# Sheet1.net
KiCad netlist of a schematic drawn in Altium Designer
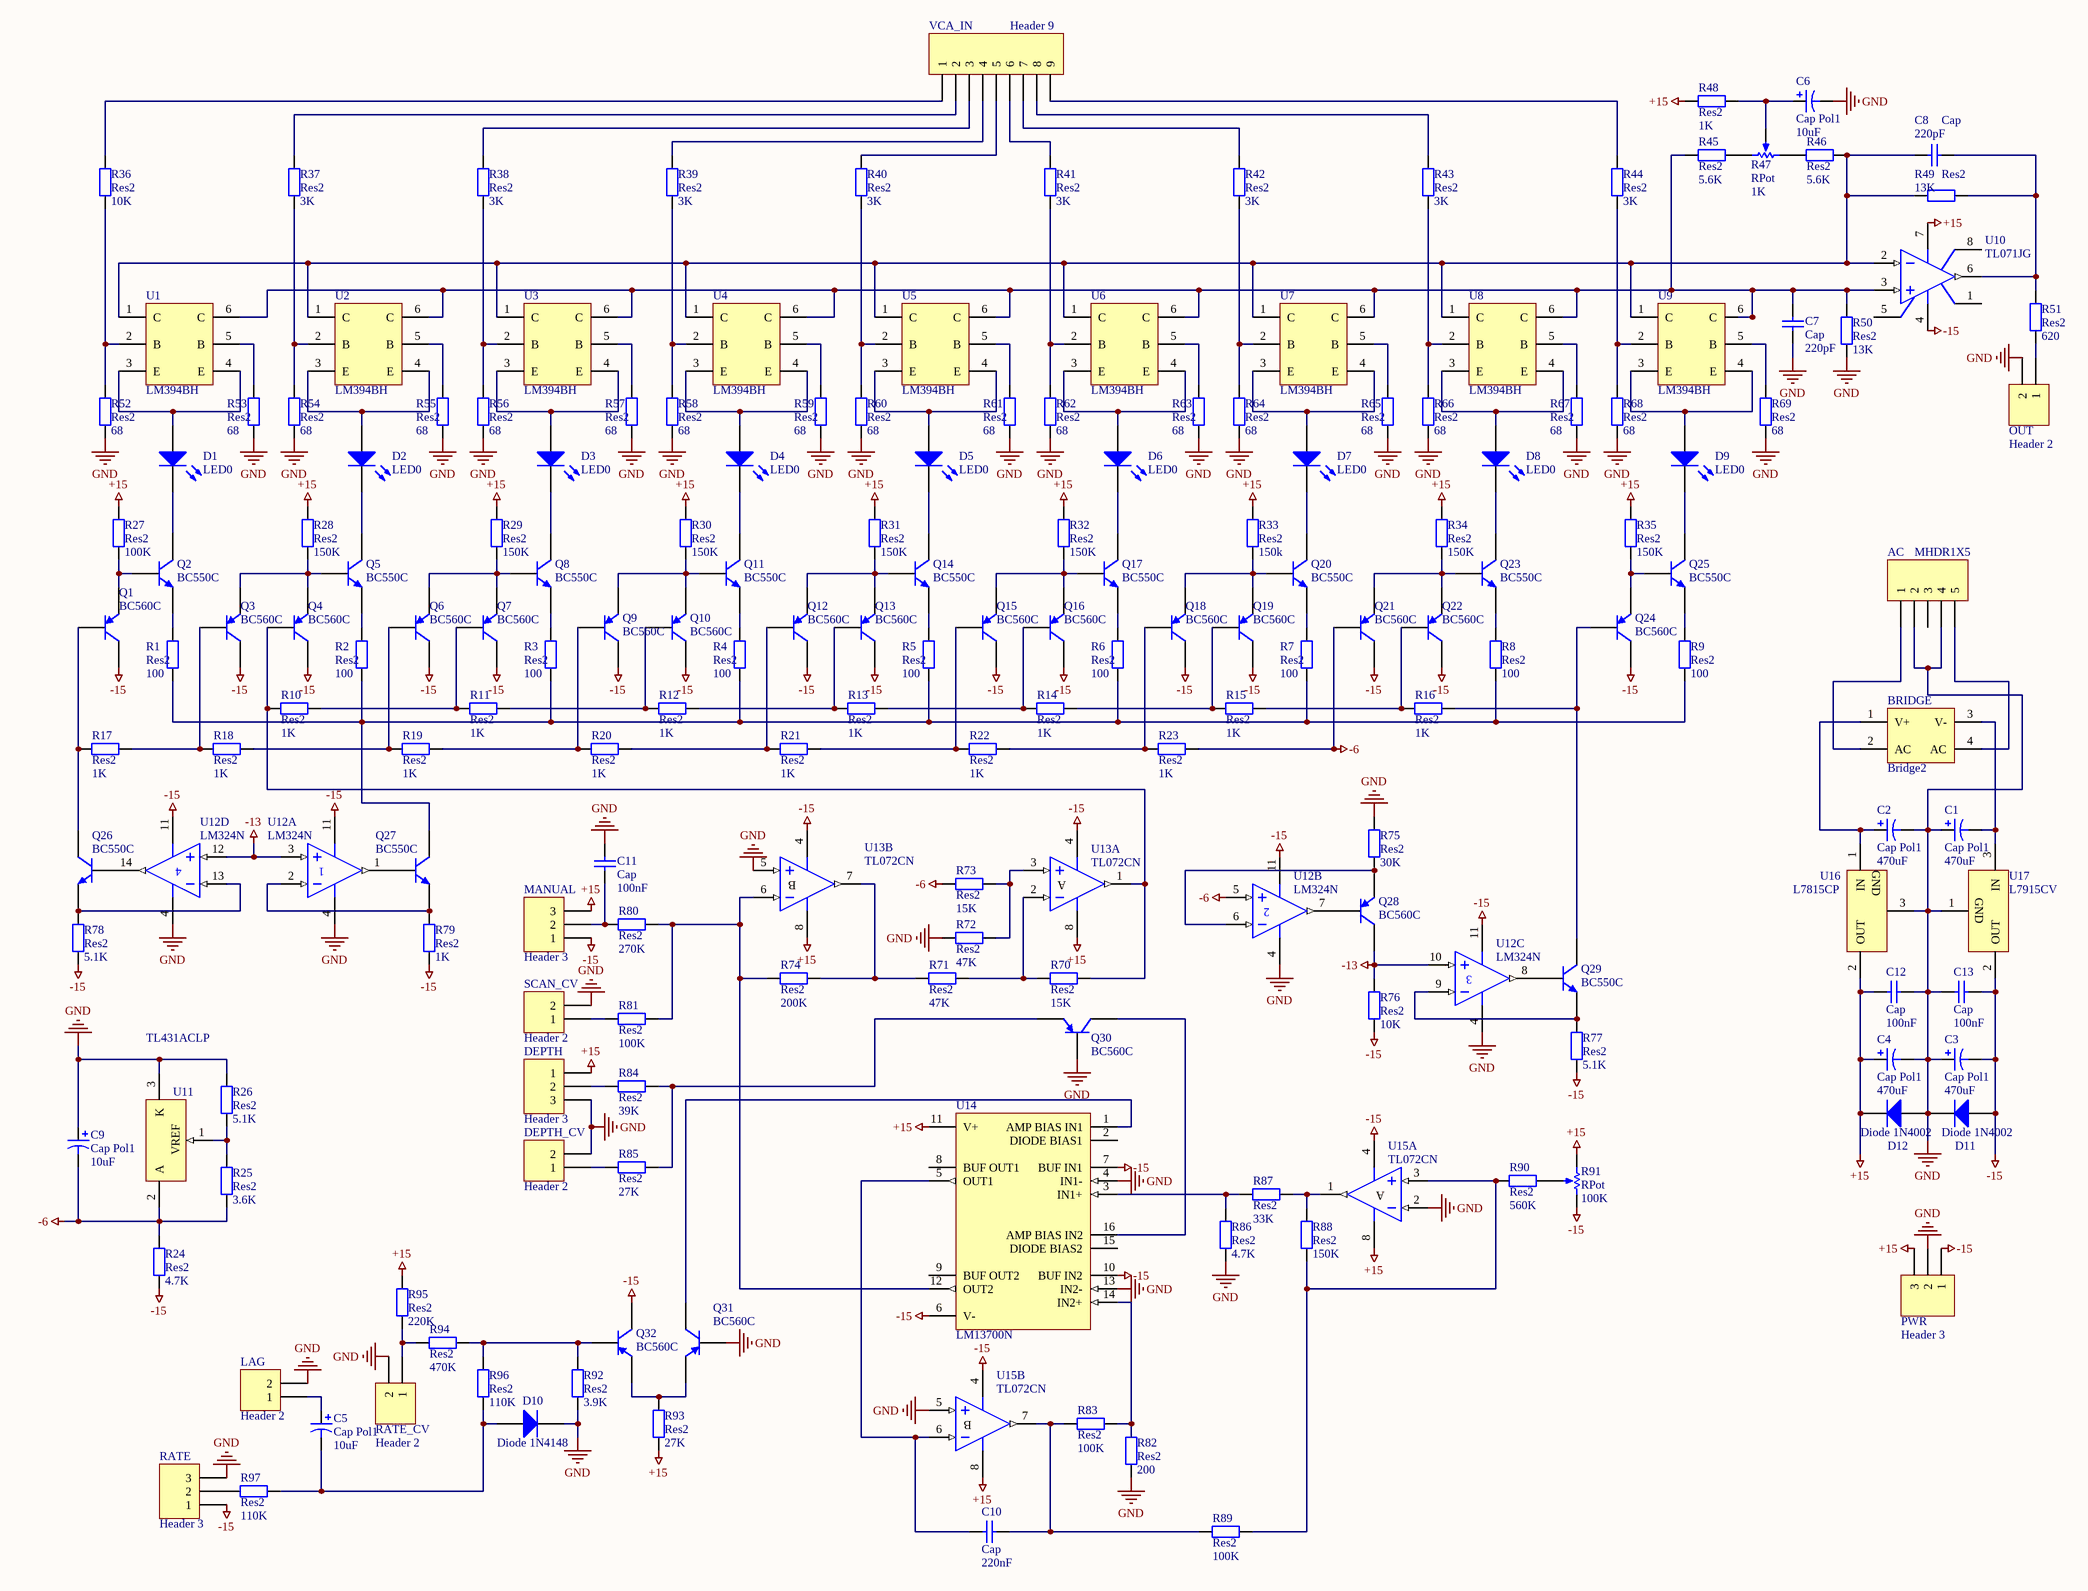
[diagram p0: Sheet1.SchDoc]

(export (version "E")
  (design (tool "Eeschema 10.0.6"))
  (components
    (comp (ref "AC")
      (value "MHDR1X5")
      (footprint "MHDR1X5")
      (description "Header, 5-Pin")
      (fields (field (name "PUBLISHER") "Altium Limited"))
      (libsource (lib "Miscellaneous Connectors") (part "MHDR1X5"))
    )
    (comp (ref "BRIDGE")
      (value "Bridge2")
      (footprint "D-46_6A")
      (description "Diode Bridge")
      (fields (field (name "PUBLISHER") "Altium Limited"))
      (libsource (lib "Miscellaneous Devices") (part "Bridge2"))
    )
    (comp (ref "C1")
      (value "Cap Pol1")
      (footprint "B")
      (description "Polarized Capacitor (Radial)")
      (fields (field (name "ALTIUM_VALUE") "470uF") (field (name "PUBLISHER") "Altium Limited"))
      (libsource (lib "Miscellaneous Devices") (part "Cap Pol1"))
    )
    (comp (ref "C2")
      (value "Cap Pol1")
      (footprint "B")
      (description "Polarized Capacitor (Radial)")
      (fields (field (name "ALTIUM_VALUE") "470uF") (field (name "PUBLISHER") "Altium Limited"))
      (libsource (lib "Miscellaneous Devices") (part "Cap Pol1"))
    )
    (comp (ref "C3")
      (value "Cap Pol1")
      (footprint "B")
      (description "Polarized Capacitor (Radial)")
      (fields (field (name "ALTIUM_VALUE") "470uF") (field (name "PUBLISHER") "Altium Limited"))
      (libsource (lib "Miscellaneous Devices") (part "Cap Pol1"))
    )
    (comp (ref "C4")
      (value "Cap Pol1")
      (footprint "B")
      (description "Polarized Capacitor (Radial)")
      (fields (field (name "ALTIUM_VALUE") "470uF") (field (name "PUBLISHER") "Altium Limited"))
      (libsource (lib "Miscellaneous Devices") (part "Cap Pol1"))
    )
    (comp (ref "C5")
      (value "Cap Pol1")
      (footprint "B")
      (description "Polarized Capacitor (Radial)")
      (fields (field (name "ALTIUM_VALUE") "10uF") (field (name "PUBLISHER") "Altium Limited"))
      (libsource (lib "Miscellaneous Devices") (part "Cap Pol1"))
    )
    (comp (ref "C6")
      (value "Cap Pol1")
      (footprint "B")
      (description "Polarized Capacitor (Radial)")
      (fields (field (name "ALTIUM_VALUE") "10uF") (field (name "PUBLISHER") "Altium Limited"))
      (libsource (lib "Miscellaneous Devices") (part "Cap Pol1"))
    )
    (comp (ref "C7")
      (value "Cap")
      (footprint "VP45-3.2")
      (description "Capacitor")
      (fields (field (name "ALTIUM_VALUE") "220pF") (field (name "PUBLISHER") "Altium Limited"))
      (libsource (lib "Miscellaneous Devices") (part "Cap"))
    )
    (comp (ref "C8")
      (value "Cap")
      (footprint "VP45-3.2")
      (description "Capacitor")
      (fields (field (name "ALTIUM_VALUE") "220pF") (field (name "PUBLISHER") "Altium Limited"))
      (libsource (lib "Miscellaneous Devices") (part "Cap"))
    )
    (comp (ref "C9")
      (value "Cap Pol1")
      (footprint "B")
      (description "Polarized Capacitor (Radial)")
      (fields (field (name "ALTIUM_VALUE") "10uF") (field (name "PUBLISHER") "Altium Limited"))
      (libsource (lib "Miscellaneous Devices") (part "Cap Pol1"))
    )
    (comp (ref "C10")
      (value "Cap")
      (footprint "VP45-3.2")
      (description "Capacitor")
      (fields (field (name "ALTIUM_VALUE") "220nF") (field (name "PUBLISHER") "Altium Limited"))
      (libsource (lib "Miscellaneous Devices") (part "Cap"))
    )
    (comp (ref "C11")
      (value "Cap")
      (footprint "VP45-3.2")
      (description "Capacitor")
      (fields (field (name "ALTIUM_VALUE") "100nF") (field (name "PUBLISHER") "Altium Limited"))
      (libsource (lib "Miscellaneous Devices") (part "Cap"))
    )
    (comp (ref "C12")
      (value "Cap")
      (footprint "VP45-3.2")
      (description "Capacitor")
      (fields (field (name "ALTIUM_VALUE") "100nF") (field (name "PUBLISHER") "Altium Limited"))
      (libsource (lib "Miscellaneous Devices") (part "Cap"))
    )
    (comp (ref "C13")
      (value "Cap")
      (footprint "VP45-3.2")
      (description "Capacitor")
      (fields (field (name "ALTIUM_VALUE") "100nF") (field (name "PUBLISHER") "Altium Limited"))
      (libsource (lib "Miscellaneous Devices") (part "Cap"))
    )
    (comp (ref "D1")
      (value "LED0")
      (footprint "LED-0")
      (description "Typical INFRARED GaAs LED")
      (fields (field (name "PUBLISHER") "Altium Limited"))
      (libsource (lib "Miscellaneous Devices") (part "LED0"))
    )
    (comp (ref "D2")
      (value "LED0")
      (footprint "LED-0")
      (description "Typical INFRARED GaAs LED")
      (fields (field (name "PUBLISHER") "Altium Limited"))
      (libsource (lib "Miscellaneous Devices") (part "LED0"))
    )
    (comp (ref "D3")
      (value "LED0")
      (footprint "LED-0")
      (description "Typical INFRARED GaAs LED")
      (fields (field (name "PUBLISHER") "Altium Limited"))
      (libsource (lib "Miscellaneous Devices") (part "LED0"))
    )
    (comp (ref "D4")
      (value "LED0")
      (footprint "LED-0")
      (description "Typical INFRARED GaAs LED")
      (fields (field (name "PUBLISHER") "Altium Limited"))
      (libsource (lib "Miscellaneous Devices") (part "LED0"))
    )
    (comp (ref "D5")
      (value "LED0")
      (footprint "LED-0")
      (description "Typical INFRARED GaAs LED")
      (fields (field (name "PUBLISHER") "Altium Limited"))
      (libsource (lib "Miscellaneous Devices") (part "LED0"))
    )
    (comp (ref "D6")
      (value "LED0")
      (footprint "LED-0")
      (description "Typical INFRARED GaAs LED")
      (fields (field (name "PUBLISHER") "Altium Limited"))
      (libsource (lib "Miscellaneous Devices") (part "LED0"))
    )
    (comp (ref "D7")
      (value "LED0")
      (footprint "LED-0")
      (description "Typical INFRARED GaAs LED")
      (fields (field (name "PUBLISHER") "Altium Limited"))
      (libsource (lib "Miscellaneous Devices") (part "LED0"))
    )
    (comp (ref "D8")
      (value "LED0")
      (footprint "LED-0")
      (description "Typical INFRARED GaAs LED")
      (fields (field (name "PUBLISHER") "Altium Limited"))
      (libsource (lib "Miscellaneous Devices") (part "LED0"))
    )
    (comp (ref "D9")
      (value "LED0")
      (footprint "LED-0")
      (description "Typical INFRARED GaAs LED")
      (fields (field (name "PUBLISHER") "Altium Limited"))
      (libsource (lib "Miscellaneous Devices") (part "LED0"))
    )
    (comp (ref "D10")
      (value "Diode 1N4148")
      (footprint "DO-35")
      (description "High Conductance Fast Diode")
      (fields (field (name "PUBLISHER") "Altium Limited"))
      (libsource (lib "Miscellaneous Devices") (part "Diode 1N4148"))
    )
    (comp (ref "D11")
      (value "Diode 1N4002")
      (footprint "DO-41")
      (description "1 Amp General Purpose Rectifier")
      (fields (field (name "PUBLISHER") "Altium Limited"))
      (libsource (lib "Miscellaneous Devices") (part "Diode 1N4002"))
    )
    (comp (ref "D12")
      (value "Diode 1N4002")
      (footprint "DO-41")
      (description "1 Amp General Purpose Rectifier")
      (fields (field (name "PUBLISHER") "Altium Limited"))
      (libsource (lib "Miscellaneous Devices") (part "Diode 1N4002"))
    )
    (comp (ref "DEPTH")
      (value "Header 3")
      (footprint "HDR1X3")
      (description "Header, 3-Pin")
      (fields (field (name "PUBLISHER") "Altium Limited"))
      (libsource (lib "") (part "Header 3_1"))
    )
    (comp (ref "DEPTH_CV")
      (value "Header 2")
      (footprint "HDR1X2")
      (description "Header, 2-Pin")
      (fields (field (name "PUBLISHER") "Altium Limited"))
      (libsource (lib "") (part "Header 2_1"))
    )
    (comp (ref "LAG")
      (value "Header 2")
      (footprint "HDR1X2")
      (description "Header, 2-Pin")
      (fields (field (name "PUBLISHER") "Altium Limited"))
      (libsource (lib "") (part "Header 2_1"))
    )
    (comp (ref "MANUAL")
      (value "Header 3")
      (footprint "HDR1X3")
      (description "Header, 3-Pin")
      (fields (field (name "PUBLISHER") "Altium Limited"))
      (libsource (lib "Miscellaneous Connectors") (part "Header 3"))
    )
    (comp (ref "OUT")
      (value "Header 2")
      (footprint "HDR1X2")
      (description "Header, 2-Pin")
      (fields (field (name "PUBLISHER") "Altium Limited"))
      (libsource (lib "Miscellaneous Connectors") (part "Header 2"))
    )
    (comp (ref "PWR")
      (value "Header 3")
      (footprint "HDR1X3")
      (description "Header, 3-Pin")
      (fields (field (name "PUBLISHER") "Altium Limited"))
      (libsource (lib "") (part "Header 3_1"))
    )
    (comp (ref "Q1")
      (value "BC560C")
      (footprint "29-04")
      (description "Low Noise Transistor PNP Silicon")
      (fields (field (name "PUBLISHER") "Altium Limited"))
      (libsource (lib "Motorola Discrete BJT") (part "BC560C"))
    )
    (comp (ref "Q2")
      (value "BC550C")
      (footprint "29-04")
      (description "Amplifier Transistor NPN Silicon")
      (fields (field (name "PUBLISHER") "Altium Limited"))
      (libsource (lib "Motorola Discrete BJT") (part "BC548C"))
    )
    (comp (ref "Q3")
      (value "BC560C")
      (footprint "29-04")
      (description "Low Noise Transistor PNP Silicon")
      (fields (field (name "PUBLISHER") "Altium Limited"))
      (libsource (lib "Motorola Discrete BJT") (part "BC560C"))
    )
    (comp (ref "Q4")
      (value "BC560C")
      (footprint "29-04")
      (description "Low Noise Transistor PNP Silicon")
      (fields (field (name "PUBLISHER") "Altium Limited"))
      (libsource (lib "Motorola Discrete BJT") (part "BC560C"))
    )
    (comp (ref "Q5")
      (value "BC550C")
      (footprint "29-04")
      (description "Amplifier Transistor NPN Silicon")
      (fields (field (name "PUBLISHER") "Altium Limited"))
      (libsource (lib "Motorola Discrete BJT") (part "BC548C"))
    )
    (comp (ref "Q6")
      (value "BC560C")
      (footprint "29-04")
      (description "Low Noise Transistor PNP Silicon")
      (fields (field (name "PUBLISHER") "Altium Limited"))
      (libsource (lib "Motorola Discrete BJT") (part "BC560C"))
    )
    (comp (ref "Q7")
      (value "BC560C")
      (footprint "29-04")
      (description "Low Noise Transistor PNP Silicon")
      (fields (field (name "PUBLISHER") "Altium Limited"))
      (libsource (lib "Motorola Discrete BJT") (part "BC560C"))
    )
    (comp (ref "Q8")
      (value "BC550C")
      (footprint "29-04")
      (description "Amplifier Transistor NPN Silicon")
      (fields (field (name "PUBLISHER") "Altium Limited"))
      (libsource (lib "Motorola Discrete BJT") (part "BC548C"))
    )
    (comp (ref "Q9")
      (value "BC560C")
      (footprint "29-04")
      (description "Low Noise Transistor PNP Silicon")
      (fields (field (name "PUBLISHER") "Altium Limited"))
      (libsource (lib "Motorola Discrete BJT") (part "BC560C"))
    )
    (comp (ref "Q10")
      (value "BC560C")
      (footprint "29-04")
      (description "Low Noise Transistor PNP Silicon")
      (fields (field (name "PUBLISHER") "Altium Limited"))
      (libsource (lib "Motorola Discrete BJT") (part "BC560C"))
    )
    (comp (ref "Q11")
      (value "BC550C")
      (footprint "29-04")
      (description "Amplifier Transistor NPN Silicon")
      (fields (field (name "PUBLISHER") "Altium Limited"))
      (libsource (lib "Motorola Discrete BJT") (part "BC548C"))
    )
    (comp (ref "Q12")
      (value "BC560C")
      (footprint "29-04")
      (description "Low Noise Transistor PNP Silicon")
      (fields (field (name "PUBLISHER") "Altium Limited"))
      (libsource (lib "Motorola Discrete BJT") (part "BC560C"))
    )
    (comp (ref "Q13")
      (value "BC560C")
      (footprint "29-04")
      (description "Low Noise Transistor PNP Silicon")
      (fields (field (name "PUBLISHER") "Altium Limited"))
      (libsource (lib "Motorola Discrete BJT") (part "BC560C"))
    )
    (comp (ref "Q14")
      (value "BC550C")
      (footprint "29-04")
      (description "Amplifier Transistor NPN Silicon")
      (fields (field (name "PUBLISHER") "Altium Limited"))
      (libsource (lib "Motorola Discrete BJT") (part "BC548C"))
    )
    (comp (ref "Q15")
      (value "BC560C")
      (footprint "29-04")
      (description "Low Noise Transistor PNP Silicon")
      (fields (field (name "PUBLISHER") "Altium Limited"))
      (libsource (lib "Motorola Discrete BJT") (part "BC560C"))
    )
    (comp (ref "Q16")
      (value "BC560C")
      (footprint "29-04")
      (description "Low Noise Transistor PNP Silicon")
      (fields (field (name "PUBLISHER") "Altium Limited"))
      (libsource (lib "Motorola Discrete BJT") (part "BC560C"))
    )
    (comp (ref "Q17")
      (value "BC550C")
      (footprint "29-04")
      (description "Amplifier Transistor NPN Silicon")
      (fields (field (name "PUBLISHER") "Altium Limited"))
      (libsource (lib "Motorola Discrete BJT") (part "BC548C"))
    )
    (comp (ref "Q18")
      (value "BC560C")
      (footprint "29-04")
      (description "Low Noise Transistor PNP Silicon")
      (fields (field (name "PUBLISHER") "Altium Limited"))
      (libsource (lib "Motorola Discrete BJT") (part "BC560C"))
    )
    (comp (ref "Q19")
      (value "BC560C")
      (footprint "29-04")
      (description "Low Noise Transistor PNP Silicon")
      (fields (field (name "PUBLISHER") "Altium Limited"))
      (libsource (lib "Motorola Discrete BJT") (part "BC560C"))
    )
    (comp (ref "Q20")
      (value "BC550C")
      (footprint "29-04")
      (description "Amplifier Transistor NPN Silicon")
      (fields (field (name "PUBLISHER") "Altium Limited"))
      (libsource (lib "Motorola Discrete BJT") (part "BC548C"))
    )
    (comp (ref "Q21")
      (value "BC560C")
      (footprint "29-04")
      (description "Low Noise Transistor PNP Silicon")
      (fields (field (name "PUBLISHER") "Altium Limited"))
      (libsource (lib "Motorola Discrete BJT") (part "BC560C"))
    )
    (comp (ref "Q22")
      (value "BC560C")
      (footprint "29-04")
      (description "Low Noise Transistor PNP Silicon")
      (fields (field (name "PUBLISHER") "Altium Limited"))
      (libsource (lib "Motorola Discrete BJT") (part "BC560C"))
    )
    (comp (ref "Q23")
      (value "BC550C")
      (footprint "29-04")
      (description "Amplifier Transistor NPN Silicon")
      (fields (field (name "PUBLISHER") "Altium Limited"))
      (libsource (lib "Motorola Discrete BJT") (part "BC548C"))
    )
    (comp (ref "Q24")
      (value "BC560C")
      (footprint "29-04")
      (description "Low Noise Transistor PNP Silicon")
      (fields (field (name "PUBLISHER") "Altium Limited"))
      (libsource (lib "Motorola Discrete BJT") (part "BC560C"))
    )
    (comp (ref "Q25")
      (value "BC550C")
      (footprint "29-04")
      (description "Amplifier Transistor NPN Silicon")
      (fields (field (name "PUBLISHER") "Altium Limited"))
      (libsource (lib "Motorola Discrete BJT") (part "BC548C"))
    )
    (comp (ref "Q26")
      (value "BC550C")
      (footprint "29-04")
      (description "Amplifier Transistor NPN Silicon")
      (fields (field (name "PUBLISHER") "Altium Limited"))
      (libsource (lib "Motorola Discrete BJT") (part "BC548C"))
    )
    (comp (ref "Q27")
      (value "BC550C")
      (footprint "29-04")
      (description "Amplifier Transistor NPN Silicon")
      (fields (field (name "PUBLISHER") "Altium Limited"))
      (libsource (lib "Motorola Discrete BJT") (part "BC548C"))
    )
    (comp (ref "Q28")
      (value "BC560C")
      (footprint "29-04")
      (description "Low Noise Transistor PNP Silicon")
      (fields (field (name "PUBLISHER") "Altium Limited"))
      (libsource (lib "Motorola Discrete BJT") (part "BC560C"))
    )
    (comp (ref "Q29")
      (value "BC550C")
      (footprint "29-04")
      (description "Amplifier Transistor NPN Silicon")
      (fields (field (name "PUBLISHER") "Altium Limited"))
      (libsource (lib "Motorola Discrete BJT") (part "BC548C"))
    )
    (comp (ref "Q30")
      (value "BC560C")
      (footprint "29-04")
      (description "Low Noise Transistor PNP Silicon")
      (fields (field (name "PUBLISHER") "Altium Limited"))
      (libsource (lib "Motorola Discrete BJT") (part "BC560C"))
    )
    (comp (ref "Q31")
      (value "BC560C")
      (footprint "29-04")
      (description "Low Noise Transistor PNP Silicon")
      (fields (field (name "PUBLISHER") "Altium Limited"))
      (libsource (lib "Motorola Discrete BJT") (part "BC560C"))
    )
    (comp (ref "Q32")
      (value "BC560C")
      (footprint "29-04")
      (description "Low Noise Transistor PNP Silicon")
      (fields (field (name "PUBLISHER") "Altium Limited"))
      (libsource (lib "Motorola Discrete BJT") (part "BC560C"))
    )
    (comp (ref "R1")
      (value "Res2")
      (footprint "AXIAL-0.4")
      (description "Resistor")
      (fields (field (name "ALTIUM_VALUE") "100") (field (name "PUBLISHER") "Altium Limited"))
      (libsource (lib "") (part "Res2_1"))
    )
    (comp (ref "R2")
      (value "Res2")
      (footprint "AXIAL-0.4")
      (description "Resistor")
      (fields (field (name "ALTIUM_VALUE") "100") (field (name "PUBLISHER") "Altium Limited"))
      (libsource (lib "") (part "Res2_1"))
    )
    (comp (ref "R3")
      (value "Res2")
      (footprint "AXIAL-0.4")
      (description "Resistor")
      (fields (field (name "ALTIUM_VALUE") "100") (field (name "PUBLISHER") "Altium Limited"))
      (libsource (lib "") (part "Res2_1"))
    )
    (comp (ref "R4")
      (value "Res2")
      (footprint "AXIAL-0.4")
      (description "Resistor")
      (fields (field (name "ALTIUM_VALUE") "100") (field (name "PUBLISHER") "Altium Limited"))
      (libsource (lib "") (part "Res2_1"))
    )
    (comp (ref "R5")
      (value "Res2")
      (footprint "AXIAL-0.4")
      (description "Resistor")
      (fields (field (name "ALTIUM_VALUE") "100") (field (name "PUBLISHER") "Altium Limited"))
      (libsource (lib "") (part "Res2_1"))
    )
    (comp (ref "R6")
      (value "Res2")
      (footprint "AXIAL-0.4")
      (description "Resistor")
      (fields (field (name "ALTIUM_VALUE") "100") (field (name "PUBLISHER") "Altium Limited"))
      (libsource (lib "") (part "Res2_1"))
    )
    (comp (ref "R7")
      (value "Res2")
      (footprint "AXIAL-0.4")
      (description "Resistor")
      (fields (field (name "ALTIUM_VALUE") "100") (field (name "PUBLISHER") "Altium Limited"))
      (libsource (lib "") (part "Res2_1"))
    )
    (comp (ref "R8")
      (value "Res2")
      (footprint "AXIAL-0.4")
      (description "Resistor")
      (fields (field (name "ALTIUM_VALUE") "100") (field (name "PUBLISHER") "Altium Limited"))
      (libsource (lib "") (part "Res2_1"))
    )
    (comp (ref "R9")
      (value "Res2")
      (footprint "AXIAL-0.4")
      (description "Resistor")
      (fields (field (name "ALTIUM_VALUE") "100") (field (name "PUBLISHER") "Altium Limited"))
      (libsource (lib "") (part "Res2_1"))
    )
    (comp (ref "R10")
      (value "Res2")
      (footprint "AXIAL-0.4")
      (description "Resistor")
      (fields (field (name "ALTIUM_VALUE") "1K") (field (name "PUBLISHER") "Altium Limited"))
      (libsource (lib "Miscellaneous Devices") (part "Res2"))
    )
    (comp (ref "R11")
      (value "Res2")
      (footprint "AXIAL-0.4")
      (description "Resistor")
      (fields (field (name "ALTIUM_VALUE") "1K") (field (name "PUBLISHER") "Altium Limited"))
      (libsource (lib "Miscellaneous Devices") (part "Res2"))
    )
    (comp (ref "R12")
      (value "Res2")
      (footprint "AXIAL-0.4")
      (description "Resistor")
      (fields (field (name "ALTIUM_VALUE") "1K") (field (name "PUBLISHER") "Altium Limited"))
      (libsource (lib "Miscellaneous Devices") (part "Res2"))
    )
    (comp (ref "R13")
      (value "Res2")
      (footprint "AXIAL-0.4")
      (description "Resistor")
      (fields (field (name "ALTIUM_VALUE") "1K") (field (name "PUBLISHER") "Altium Limited"))
      (libsource (lib "Miscellaneous Devices") (part "Res2"))
    )
    (comp (ref "R14")
      (value "Res2")
      (footprint "AXIAL-0.4")
      (description "Resistor")
      (fields (field (name "ALTIUM_VALUE") "1K") (field (name "PUBLISHER") "Altium Limited"))
      (libsource (lib "Miscellaneous Devices") (part "Res2"))
    )
    (comp (ref "R15")
      (value "Res2")
      (footprint "AXIAL-0.4")
      (description "Resistor")
      (fields (field (name "ALTIUM_VALUE") "1K") (field (name "PUBLISHER") "Altium Limited"))
      (libsource (lib "Miscellaneous Devices") (part "Res2"))
    )
    (comp (ref "R16")
      (value "Res2")
      (footprint "AXIAL-0.4")
      (description "Resistor")
      (fields (field (name "ALTIUM_VALUE") "1K") (field (name "PUBLISHER") "Altium Limited"))
      (libsource (lib "Miscellaneous Devices") (part "Res2"))
    )
    (comp (ref "R17")
      (value "Res2")
      (footprint "AXIAL-0.4")
      (description "Resistor")
      (fields (field (name "ALTIUM_VALUE") "1K") (field (name "PUBLISHER") "Altium Limited"))
      (libsource (lib "Miscellaneous Devices") (part "Res2"))
    )
    (comp (ref "R18")
      (value "Res2")
      (footprint "AXIAL-0.4")
      (description "Resistor")
      (fields (field (name "ALTIUM_VALUE") "1K") (field (name "PUBLISHER") "Altium Limited"))
      (libsource (lib "Miscellaneous Devices") (part "Res2"))
    )
    (comp (ref "R19")
      (value "Res2")
      (footprint "AXIAL-0.4")
      (description "Resistor")
      (fields (field (name "ALTIUM_VALUE") "1K") (field (name "PUBLISHER") "Altium Limited"))
      (libsource (lib "Miscellaneous Devices") (part "Res2"))
    )
    (comp (ref "R20")
      (value "Res2")
      (footprint "AXIAL-0.4")
      (description "Resistor")
      (fields (field (name "ALTIUM_VALUE") "1K") (field (name "PUBLISHER") "Altium Limited"))
      (libsource (lib "Miscellaneous Devices") (part "Res2"))
    )
    (comp (ref "R21")
      (value "Res2")
      (footprint "AXIAL-0.4")
      (description "Resistor")
      (fields (field (name "ALTIUM_VALUE") "1K") (field (name "PUBLISHER") "Altium Limited"))
      (libsource (lib "Miscellaneous Devices") (part "Res2"))
    )
    (comp (ref "R22")
      (value "Res2")
      (footprint "AXIAL-0.4")
      (description "Resistor")
      (fields (field (name "ALTIUM_VALUE") "1K") (field (name "PUBLISHER") "Altium Limited"))
      (libsource (lib "Miscellaneous Devices") (part "Res2"))
    )
    (comp (ref "R23")
      (value "Res2")
      (footprint "AXIAL-0.4")
      (description "Resistor")
      (fields (field (name "ALTIUM_VALUE") "1K") (field (name "PUBLISHER") "Altium Limited"))
      (libsource (lib "Miscellaneous Devices") (part "Res2"))
    )
    (comp (ref "R24")
      (value "Res2")
      (footprint "AXIAL-0.4")
      (description "Resistor")
      (fields (field (name "ALTIUM_VALUE") "4.7K") (field (name "PUBLISHER") "Altium Limited"))
      (libsource (lib "") (part "Res2_1"))
    )
    (comp (ref "R25")
      (value "Res2")
      (footprint "AXIAL-0.4")
      (description "Resistor")
      (fields (field (name "ALTIUM_VALUE") "3.6K") (field (name "PUBLISHER") "Altium Limited"))
      (libsource (lib "") (part "Res2_1"))
    )
    (comp (ref "R26")
      (value "Res2")
      (footprint "AXIAL-0.4")
      (description "Resistor")
      (fields (field (name "ALTIUM_VALUE") "5.1K") (field (name "PUBLISHER") "Altium Limited"))
      (libsource (lib "") (part "Res2_1"))
    )
    (comp (ref "R27")
      (value "Res2")
      (footprint "AXIAL-0.4")
      (description "Resistor")
      (fields (field (name "ALTIUM_VALUE") "100K") (field (name "PUBLISHER") "Altium Limited"))
      (libsource (lib "") (part "Res2_1"))
    )
    (comp (ref "R28")
      (value "Res2")
      (footprint "AXIAL-0.4")
      (description "Resistor")
      (fields (field (name "ALTIUM_VALUE") "150K") (field (name "PUBLISHER") "Altium Limited"))
      (libsource (lib "") (part "Res2_1"))
    )
    (comp (ref "R29")
      (value "Res2")
      (footprint "AXIAL-0.4")
      (description "Resistor")
      (fields (field (name "ALTIUM_VALUE") "150K") (field (name "PUBLISHER") "Altium Limited"))
      (libsource (lib "") (part "Res2_1"))
    )
    (comp (ref "R30")
      (value "Res2")
      (footprint "AXIAL-0.4")
      (description "Resistor")
      (fields (field (name "ALTIUM_VALUE") "150K") (field (name "PUBLISHER") "Altium Limited"))
      (libsource (lib "") (part "Res2_1"))
    )
    (comp (ref "R31")
      (value "Res2")
      (footprint "AXIAL-0.4")
      (description "Resistor")
      (fields (field (name "ALTIUM_VALUE") "150K") (field (name "PUBLISHER") "Altium Limited"))
      (libsource (lib "") (part "Res2_1"))
    )
    (comp (ref "R32")
      (value "Res2")
      (footprint "AXIAL-0.4")
      (description "Resistor")
      (fields (field (name "ALTIUM_VALUE") "150K") (field (name "PUBLISHER") "Altium Limited"))
      (libsource (lib "") (part "Res2_1"))
    )
    (comp (ref "R33")
      (value "Res2")
      (footprint "AXIAL-0.4")
      (description "Resistor")
      (fields (field (name "ALTIUM_VALUE") "150k") (field (name "PUBLISHER") "Altium Limited"))
      (libsource (lib "") (part "Res2_1"))
    )
    (comp (ref "R34")
      (value "Res2")
      (footprint "AXIAL-0.4")
      (description "Resistor")
      (fields (field (name "ALTIUM_VALUE") "150K") (field (name "PUBLISHER") "Altium Limited"))
      (libsource (lib "") (part "Res2_1"))
    )
    (comp (ref "R35")
      (value "Res2")
      (footprint "AXIAL-0.4")
      (description "Resistor")
      (fields (field (name "ALTIUM_VALUE") "150K") (field (name "PUBLISHER") "Altium Limited"))
      (libsource (lib "") (part "Res2_1"))
    )
    (comp (ref "R36")
      (value "Res2")
      (footprint "AXIAL-0.4")
      (description "Resistor")
      (fields (field (name "ALTIUM_VALUE") "10K") (field (name "PUBLISHER") "Altium Limited"))
      (libsource (lib "") (part "Res2_1"))
    )
    (comp (ref "R37")
      (value "Res2")
      (footprint "AXIAL-0.4")
      (description "Resistor")
      (fields (field (name "ALTIUM_VALUE") "3K") (field (name "PUBLISHER") "Altium Limited"))
      (libsource (lib "") (part "Res2_1"))
    )
    (comp (ref "R38")
      (value "Res2")
      (footprint "AXIAL-0.4")
      (description "Resistor")
      (fields (field (name "ALTIUM_VALUE") "3K") (field (name "PUBLISHER") "Altium Limited"))
      (libsource (lib "") (part "Res2_1"))
    )
    (comp (ref "R39")
      (value "Res2")
      (footprint "AXIAL-0.4")
      (description "Resistor")
      (fields (field (name "ALTIUM_VALUE") "3K") (field (name "PUBLISHER") "Altium Limited"))
      (libsource (lib "") (part "Res2_1"))
    )
    (comp (ref "R40")
      (value "Res2")
      (footprint "AXIAL-0.4")
      (description "Resistor")
      (fields (field (name "ALTIUM_VALUE") "3K") (field (name "PUBLISHER") "Altium Limited"))
      (libsource (lib "") (part "Res2_1"))
    )
    (comp (ref "R41")
      (value "Res2")
      (footprint "AXIAL-0.4")
      (description "Resistor")
      (fields (field (name "ALTIUM_VALUE") "3K") (field (name "PUBLISHER") "Altium Limited"))
      (libsource (lib "") (part "Res2_1"))
    )
    (comp (ref "R42")
      (value "Res2")
      (footprint "AXIAL-0.4")
      (description "Resistor")
      (fields (field (name "ALTIUM_VALUE") "3K") (field (name "PUBLISHER") "Altium Limited"))
      (libsource (lib "") (part "Res2_1"))
    )
    (comp (ref "R43")
      (value "Res2")
      (footprint "AXIAL-0.4")
      (description "Resistor")
      (fields (field (name "ALTIUM_VALUE") "3K") (field (name "PUBLISHER") "Altium Limited"))
      (libsource (lib "") (part "Res2_1"))
    )
    (comp (ref "R44")
      (value "Res2")
      (footprint "AXIAL-0.4")
      (description "Resistor")
      (fields (field (name "ALTIUM_VALUE") "3K") (field (name "PUBLISHER") "Altium Limited"))
      (libsource (lib "") (part "Res2_1"))
    )
    (comp (ref "R45")
      (value "Res2")
      (footprint "AXIAL-0.4")
      (description "Resistor")
      (fields (field (name "ALTIUM_VALUE") "5.6K") (field (name "PUBLISHER") "Altium Limited"))
      (libsource (lib "") (part "Res2_3"))
    )
    (comp (ref "R46")
      (value "Res2")
      (footprint "AXIAL-0.4")
      (description "Resistor")
      (fields (field (name "ALTIUM_VALUE") "5.6K") (field (name "PUBLISHER") "Altium Limited"))
      (libsource (lib "") (part "Res2_3"))
    )
    (comp (ref "R47")
      (value "RPot")
      (footprint "VR5")
      (description "Potentiometer")
      (fields (field (name "ALTIUM_VALUE") "1K") (field (name "PUBLISHER") "Altium Limited"))
      (libsource (lib "Miscellaneous Devices") (part "RPot"))
    )
    (comp (ref "R48")
      (value "Res2")
      (footprint "AXIAL-0.4")
      (description "Resistor")
      (fields (field (name "ALTIUM_VALUE") "1K") (field (name "PUBLISHER") "Altium Limited"))
      (libsource (lib "") (part "Res2_3"))
    )
    (comp (ref "R49")
      (value "Res2")
      (footprint "AXIAL-0.4")
      (description "Resistor")
      (fields (field (name "ALTIUM_VALUE") "13K") (field (name "PUBLISHER") "Altium Limited"))
      (libsource (lib "") (part "Res2_3"))
    )
    (comp (ref "R50")
      (value "Res2")
      (footprint "AXIAL-0.4")
      (description "Resistor")
      (fields (field (name "ALTIUM_VALUE") "13K") (field (name "PUBLISHER") "Altium Limited"))
      (libsource (lib "") (part "Res2_1"))
    )
    (comp (ref "R51")
      (value "Res2")
      (footprint "AXIAL-0.4")
      (description "Resistor")
      (fields (field (name "ALTIUM_VALUE") "620") (field (name "PUBLISHER") "Altium Limited"))
      (libsource (lib "") (part "Res2_1"))
    )
    (comp (ref "R52")
      (value "Res2")
      (footprint "AXIAL-0.4")
      (description "Resistor")
      (fields (field (name "ALTIUM_VALUE") "68") (field (name "PUBLISHER") "Altium Limited"))
      (libsource (lib "") (part "Res2_1"))
    )
    (comp (ref "R53")
      (value "Res2")
      (footprint "AXIAL-0.4")
      (description "Resistor")
      (fields (field (name "ALTIUM_VALUE") "68") (field (name "PUBLISHER") "Altium Limited"))
      (libsource (lib "") (part "Res2_1"))
    )
    (comp (ref "R54")
      (value "Res2")
      (footprint "AXIAL-0.4")
      (description "Resistor")
      (fields (field (name "ALTIUM_VALUE") "68") (field (name "PUBLISHER") "Altium Limited"))
      (libsource (lib "") (part "Res2_1"))
    )
    (comp (ref "R55")
      (value "Res2")
      (footprint "AXIAL-0.4")
      (description "Resistor")
      (fields (field (name "ALTIUM_VALUE") "68") (field (name "PUBLISHER") "Altium Limited"))
      (libsource (lib "") (part "Res2_1"))
    )
    (comp (ref "R56")
      (value "Res2")
      (footprint "AXIAL-0.4")
      (description "Resistor")
      (fields (field (name "ALTIUM_VALUE") "68") (field (name "PUBLISHER") "Altium Limited"))
      (libsource (lib "") (part "Res2_1"))
    )
    (comp (ref "R57")
      (value "Res2")
      (footprint "AXIAL-0.4")
      (description "Resistor")
      (fields (field (name "ALTIUM_VALUE") "68") (field (name "PUBLISHER") "Altium Limited"))
      (libsource (lib "") (part "Res2_1"))
    )
    (comp (ref "R58")
      (value "Res2")
      (footprint "AXIAL-0.4")
      (description "Resistor")
      (fields (field (name "ALTIUM_VALUE") "68") (field (name "PUBLISHER") "Altium Limited"))
      (libsource (lib "") (part "Res2_1"))
    )
    (comp (ref "R59")
      (value "Res2")
      (footprint "AXIAL-0.4")
      (description "Resistor")
      (fields (field (name "ALTIUM_VALUE") "68") (field (name "PUBLISHER") "Altium Limited"))
      (libsource (lib "") (part "Res2_1"))
    )
    (comp (ref "R60")
      (value "Res2")
      (footprint "AXIAL-0.4")
      (description "Resistor")
      (fields (field (name "ALTIUM_VALUE") "68") (field (name "PUBLISHER") "Altium Limited"))
      (libsource (lib "") (part "Res2_1"))
    )
    (comp (ref "R61")
      (value "Res2")
      (footprint "AXIAL-0.4")
      (description "Resistor")
      (fields (field (name "ALTIUM_VALUE") "68") (field (name "PUBLISHER") "Altium Limited"))
      (libsource (lib "") (part "Res2_1"))
    )
    (comp (ref "R62")
      (value "Res2")
      (footprint "AXIAL-0.4")
      (description "Resistor")
      (fields (field (name "ALTIUM_VALUE") "68") (field (name "PUBLISHER") "Altium Limited"))
      (libsource (lib "") (part "Res2_1"))
    )
    (comp (ref "R63")
      (value "Res2")
      (footprint "AXIAL-0.4")
      (description "Resistor")
      (fields (field (name "ALTIUM_VALUE") "68") (field (name "PUBLISHER") "Altium Limited"))
      (libsource (lib "") (part "Res2_1"))
    )
    (comp (ref "R64")
      (value "Res2")
      (footprint "AXIAL-0.4")
      (description "Resistor")
      (fields (field (name "ALTIUM_VALUE") "68") (field (name "PUBLISHER") "Altium Limited"))
      (libsource (lib "") (part "Res2_1"))
    )
    (comp (ref "R65")
      (value "Res2")
      (footprint "AXIAL-0.4")
      (description "Resistor")
      (fields (field (name "ALTIUM_VALUE") "68") (field (name "PUBLISHER") "Altium Limited"))
      (libsource (lib "") (part "Res2_1"))
    )
    (comp (ref "R66")
      (value "Res2")
      (footprint "AXIAL-0.4")
      (description "Resistor")
      (fields (field (name "ALTIUM_VALUE") "68") (field (name "PUBLISHER") "Altium Limited"))
      (libsource (lib "") (part "Res2_1"))
    )
    (comp (ref "R67")
      (value "Res2")
      (footprint "AXIAL-0.4")
      (description "Resistor")
      (fields (field (name "ALTIUM_VALUE") "68") (field (name "PUBLISHER") "Altium Limited"))
      (libsource (lib "") (part "Res2_1"))
    )
    (comp (ref "R68")
      (value "Res2")
      (footprint "AXIAL-0.4")
      (description "Resistor")
      (fields (field (name "ALTIUM_VALUE") "68") (field (name "PUBLISHER") "Altium Limited"))
      (libsource (lib "") (part "Res2_1"))
    )
    (comp (ref "R69")
      (value "Res2")
      (footprint "AXIAL-0.4")
      (description "Resistor")
      (fields (field (name "ALTIUM_VALUE") "68") (field (name "PUBLISHER") "Altium Limited"))
      (libsource (lib "") (part "Res2_1"))
    )
    (comp (ref "R70")
      (value "Res2")
      (footprint "AXIAL-0.4")
      (description "Resistor")
      (fields (field (name "ALTIUM_VALUE") "15K") (field (name "PUBLISHER") "Altium Limited"))
      (libsource (lib "Miscellaneous Devices") (part "Res2"))
    )
    (comp (ref "R71")
      (value "Res2")
      (footprint "AXIAL-0.4")
      (description "Resistor")
      (fields (field (name "ALTIUM_VALUE") "47K") (field (name "PUBLISHER") "Altium Limited"))
      (libsource (lib "Miscellaneous Devices") (part "Res2"))
    )
    (comp (ref "R72")
      (value "Res2")
      (footprint "AXIAL-0.4")
      (description "Resistor")
      (fields (field (name "ALTIUM_VALUE") "47K") (field (name "PUBLISHER") "Altium Limited"))
      (libsource (lib "") (part "Res2_3"))
    )
    (comp (ref "R73")
      (value "Res2")
      (footprint "AXIAL-0.4")
      (description "Resistor")
      (fields (field (name "ALTIUM_VALUE") "15K") (field (name "PUBLISHER") "Altium Limited"))
      (libsource (lib "Miscellaneous Devices") (part "Res2"))
    )
    (comp (ref "R74")
      (value "Res2")
      (footprint "AXIAL-0.4")
      (description "Resistor")
      (fields (field (name "ALTIUM_VALUE") "200K") (field (name "PUBLISHER") "Altium Limited"))
      (libsource (lib "Miscellaneous Devices") (part "Res2"))
    )
    (comp (ref "R75")
      (value "Res2")
      (footprint "AXIAL-0.4")
      (description "Resistor")
      (fields (field (name "ALTIUM_VALUE") "30K") (field (name "PUBLISHER") "Altium Limited"))
      (libsource (lib "") (part "Res2_1"))
    )
    (comp (ref "R76")
      (value "Res2")
      (footprint "AXIAL-0.4")
      (description "Resistor")
      (fields (field (name "ALTIUM_VALUE") "10K") (field (name "PUBLISHER") "Altium Limited"))
      (libsource (lib "") (part "Res2_1"))
    )
    (comp (ref "R77")
      (value "Res2")
      (footprint "AXIAL-0.4")
      (description "Resistor")
      (fields (field (name "ALTIUM_VALUE") "5.1K") (field (name "PUBLISHER") "Altium Limited"))
      (libsource (lib "") (part "Res2_1"))
    )
    (comp (ref "R78")
      (value "Res2")
      (footprint "AXIAL-0.4")
      (description "Resistor")
      (fields (field (name "ALTIUM_VALUE") "5.1K") (field (name "PUBLISHER") "Altium Limited"))
      (libsource (lib "") (part "Res2_1"))
    )
    (comp (ref "R79")
      (value "Res2")
      (footprint "AXIAL-0.4")
      (description "Resistor")
      (fields (field (name "ALTIUM_VALUE") "1K") (field (name "PUBLISHER") "Altium Limited"))
      (libsource (lib "") (part "Res2_1"))
    )
    (comp (ref "R80")
      (value "Res2")
      (footprint "AXIAL-0.4")
      (description "Resistor")
      (fields (field (name "ALTIUM_VALUE") "270K") (field (name "PUBLISHER") "Altium Limited"))
      (libsource (lib "Miscellaneous Devices") (part "Res2"))
    )
    (comp (ref "R81")
      (value "Res2")
      (footprint "AXIAL-0.4")
      (description "Resistor")
      (fields (field (name "ALTIUM_VALUE") "100K") (field (name "PUBLISHER") "Altium Limited"))
      (libsource (lib "Miscellaneous Devices") (part "Res2"))
    )
    (comp (ref "R82")
      (value "Res2")
      (footprint "AXIAL-0.4")
      (description "Resistor")
      (fields (field (name "ALTIUM_VALUE") "200") (field (name "PUBLISHER") "Altium Limited"))
      (libsource (lib "Miscellaneous Devices") (part "Res2"))
    )
    (comp (ref "R83")
      (value "Res2")
      (footprint "AXIAL-0.4")
      (description "Resistor")
      (fields (field (name "ALTIUM_VALUE") "100K") (field (name "PUBLISHER") "Altium Limited"))
      (libsource (lib "") (part "Res2_2"))
    )
    (comp (ref "R84")
      (value "Res2")
      (footprint "AXIAL-0.4")
      (description "Resistor")
      (fields (field (name "ALTIUM_VALUE") "39K") (field (name "PUBLISHER") "Altium Limited"))
      (libsource (lib "Miscellaneous Devices") (part "Res2"))
    )
    (comp (ref "R85")
      (value "Res2")
      (footprint "AXIAL-0.4")
      (description "Resistor")
      (fields (field (name "ALTIUM_VALUE") "27K") (field (name "PUBLISHER") "Altium Limited"))
      (libsource (lib "Miscellaneous Devices") (part "Res2"))
    )
    (comp (ref "R86")
      (value "Res2")
      (footprint "AXIAL-0.4")
      (description "Resistor")
      (fields (field (name "ALTIUM_VALUE") "4.7K") (field (name "PUBLISHER") "Altium Limited"))
      (libsource (lib "") (part "Res2_2"))
    )
    (comp (ref "R87")
      (value "Res2")
      (footprint "AXIAL-0.4")
      (description "Resistor")
      (fields (field (name "ALTIUM_VALUE") "33K") (field (name "PUBLISHER") "Altium Limited"))
      (libsource (lib "") (part "Res2_3"))
    )
    (comp (ref "R88")
      (value "Res2")
      (footprint "AXIAL-0.4")
      (description "Resistor")
      (fields (field (name "ALTIUM_VALUE") "150K") (field (name "PUBLISHER") "Altium Limited"))
      (libsource (lib "") (part "Res2_1"))
    )
    (comp (ref "R89")
      (value "Res2")
      (footprint "AXIAL-0.4")
      (description "Resistor")
      (fields (field (name "ALTIUM_VALUE") "100K") (field (name "PUBLISHER") "Altium Limited"))
      (libsource (lib "") (part "Res2_3"))
    )
    (comp (ref "R90")
      (value "Res2")
      (footprint "AXIAL-0.4")
      (description "Resistor")
      (fields (field (name "ALTIUM_VALUE") "560K") (field (name "PUBLISHER") "Altium Limited"))
      (libsource (lib "Miscellaneous Devices") (part "Res2"))
    )
    (comp (ref "R91")
      (value "RPot")
      (footprint "VR5")
      (description "Potentiometer")
      (fields (field (name "ALTIUM_VALUE") "100K") (field (name "PUBLISHER") "Altium Limited"))
      (libsource (lib "Miscellaneous Devices") (part "RPot"))
    )
    (comp (ref "R92")
      (value "Res2")
      (footprint "AXIAL-0.4")
      (description "Resistor")
      (fields (field (name "ALTIUM_VALUE") "3.9K") (field (name "PUBLISHER") "Altium Limited"))
      (libsource (lib "") (part "Res2_1"))
    )
    (comp (ref "R93")
      (value "Res2")
      (footprint "AXIAL-0.4")
      (description "Resistor")
      (fields (field (name "ALTIUM_VALUE") "27K") (field (name "PUBLISHER") "Altium Limited"))
      (libsource (lib "") (part "Res2_1"))
    )
    (comp (ref "R94")
      (value "Res2")
      (footprint "AXIAL-0.4")
      (description "Resistor")
      (fields (field (name "ALTIUM_VALUE") "470K") (field (name "PUBLISHER") "Altium Limited"))
      (libsource (lib "Miscellaneous Devices") (part "Res2"))
    )
    (comp (ref "R95")
      (value "Res2")
      (footprint "AXIAL-0.4")
      (description "Resistor")
      (fields (field (name "ALTIUM_VALUE") "220K") (field (name "PUBLISHER") "Altium Limited"))
      (libsource (lib "") (part "Res2_1"))
    )
    (comp (ref "R96")
      (value "Res2")
      (footprint "AXIAL-0.4")
      (description "Resistor")
      (fields (field (name "ALTIUM_VALUE") "110K") (field (name "PUBLISHER") "Altium Limited"))
      (libsource (lib "") (part "Res2_1"))
    )
    (comp (ref "R97")
      (value "Res2")
      (footprint "AXIAL-0.4")
      (description "Resistor")
      (fields (field (name "ALTIUM_VALUE") "110K") (field (name "PUBLISHER") "Altium Limited"))
      (libsource (lib "Miscellaneous Devices") (part "Res2"))
    )
    (comp (ref "RATE")
      (value "Header 3")
      (footprint "HDR1X3")
      (description "Header, 3-Pin")
      (fields (field (name "PUBLISHER") "Altium Limited"))
      (libsource (lib "Miscellaneous Connectors") (part "Header 3"))
    )
    (comp (ref "RATE_CV")
      (value "Header 2")
      (footprint "HDR1X2")
      (description "Header, 2-Pin")
      (fields (field (name "PUBLISHER") "Altium Limited"))
      (libsource (lib "Miscellaneous Connectors") (part "Header 2"))
    )
    (comp (ref "SCAN_CV")
      (value "Header 2")
      (footprint "HDR1X2")
      (description "Header, 2-Pin")
      (fields (field (name "PUBLISHER") "Altium Limited"))
      (libsource (lib "") (part "Header 2_1"))
    )
    (comp (ref "U1")
      (value "LM394BH")
      (footprint "H06C")
      (description "Supermatch Pair")
      (fields
        (field (name "MANUFACTURER") "National Semiconductor")
        (field (name "DIGIKEYPARTNUMBER") "LM394BH-ND")
        (field (name "PUBLISHER") "Altium Limited")
      )
      (libsource (lib "NSC Amplifier") (part "LM394BH"))
    )
    (comp (ref "U2")
      (value "LM394BH")
      (footprint "H06C")
      (description "Supermatch Pair")
      (fields
        (field (name "MANUFACTURER") "National Semiconductor")
        (field (name "DIGIKEYPARTNUMBER") "LM394BH-ND")
        (field (name "PUBLISHER") "Altium Limited")
      )
      (libsource (lib "NSC Amplifier") (part "LM394BH"))
    )
    (comp (ref "U3")
      (value "LM394BH")
      (footprint "H06C")
      (description "Supermatch Pair")
      (fields
        (field (name "MANUFACTURER") "National Semiconductor")
        (field (name "DIGIKEYPARTNUMBER") "LM394BH-ND")
        (field (name "PUBLISHER") "Altium Limited")
      )
      (libsource (lib "NSC Amplifier") (part "LM394BH"))
    )
    (comp (ref "U4")
      (value "LM394BH")
      (footprint "H06C")
      (description "Supermatch Pair")
      (fields
        (field (name "MANUFACTURER") "National Semiconductor")
        (field (name "DIGIKEYPARTNUMBER") "LM394BH-ND")
        (field (name "PUBLISHER") "Altium Limited")
      )
      (libsource (lib "NSC Amplifier") (part "LM394BH"))
    )
    (comp (ref "U5")
      (value "LM394BH")
      (footprint "H06C")
      (description "Supermatch Pair")
      (fields
        (field (name "MANUFACTURER") "National Semiconductor")
        (field (name "DIGIKEYPARTNUMBER") "LM394BH-ND")
        (field (name "PUBLISHER") "Altium Limited")
      )
      (libsource (lib "NSC Amplifier") (part "LM394BH"))
    )
    (comp (ref "U6")
      (value "LM394BH")
      (footprint "H06C")
      (description "Supermatch Pair")
      (fields
        (field (name "MANUFACTURER") "National Semiconductor")
        (field (name "DIGIKEYPARTNUMBER") "LM394BH-ND")
        (field (name "PUBLISHER") "Altium Limited")
      )
      (libsource (lib "NSC Amplifier") (part "LM394BH"))
    )
    (comp (ref "U7")
      (value "LM394BH")
      (footprint "H06C")
      (description "Supermatch Pair")
      (fields
        (field (name "MANUFACTURER") "National Semiconductor")
        (field (name "DIGIKEYPARTNUMBER") "LM394BH-ND")
        (field (name "PUBLISHER") "Altium Limited")
      )
      (libsource (lib "NSC Amplifier") (part "LM394BH"))
    )
    (comp (ref "U8")
      (value "LM394BH")
      (footprint "H06C")
      (description "Supermatch Pair")
      (fields
        (field (name "MANUFACTURER") "National Semiconductor")
        (field (name "DIGIKEYPARTNUMBER") "LM394BH-ND")
        (field (name "PUBLISHER") "Altium Limited")
      )
      (libsource (lib "NSC Amplifier") (part "LM394BH"))
    )
    (comp (ref "U9")
      (value "LM394BH")
      (footprint "H06C")
      (description "Supermatch Pair")
      (fields
        (field (name "MANUFACTURER") "National Semiconductor")
        (field (name "DIGIKEYPARTNUMBER") "LM394BH-ND")
        (field (name "PUBLISHER") "Altium Limited")
      )
      (libsource (lib "NSC Amplifier") (part "LM394BH"))
    )
    (comp (ref "U10")
      (value "TL071JG")
      (footprint "JG008")
      (description "Low-Noise JFET-Input Operational Amplifier")
      (fields (field (name "PUBLISHER") "Altium Limited"))
      (libsource (lib "TI Operational Amplifier") (part "TL071JG"))
    )
    (comp (ref "U11")
      (value "TL431ACLP")
      (footprint "LP03")
      (description "Adjustable Precision Shunt Regulator")
      (fields (field (name "PUBLISHER") "Altium Limited"))
      (libsource (lib "TI Power Mgt Voltage Regulator") (part "TL431ACLP"))
    )
    (comp (ref "U12")
      (value "LM324N")
      (footprint "646-06")
      (description "Quad Low-Power Operational Amplifier")
      (fields (field (name "PUBLISHER") "Altium Limited"))
      (libsource (lib "Motorola Amplifier Operational Amplifier") (part "LM324N"))
    )
    (comp (ref "U13")
      (value "TL072CN")
      (footprint "DIP8")
      (description "Low-Noise J-FET Dual Operational Amplifier")
      (fields (field (name "PUBLISHER") "Altium Limited"))
      (libsource (lib "ST Operational Amplifier") (part "TL072CN"))
    )
    (comp (ref "U14")
      (value "LM13700N")
      (footprint "N16E")
      (description "Dual Operational Transconductance Amplifier with Linearizing Diodes and Buffers")
      (fields
        (field (name "MANUFACTURER") "National Semiconductor")
        (field (name "DIGIKEYPARTNUMBER") "LM13700N-ND")
        (field (name "PUBLISHER") "Altium Limited")
      )
      (libsource (lib "NSC Amplifier") (part "LM13700N"))
    )
    (comp (ref "U15")
      (value "TL072CN")
      (footprint "DIP8")
      (description "Low-Noise J-FET Dual Operational Amplifier")
      (fields (field (name "PUBLISHER") "Altium Limited"))
      (libsource (lib "ST Operational Amplifier") (part "TL072CN"))
    )
    (comp (ref "U16")
      (value "L7815CP")
      (footprint "ISOWATT220AB")
      (description "Positive Voltage Regulator")
      (fields (field (name "PUBLISHER") "Altium Limited"))
      (libsource (lib "ST Power Mgt Voltage Regulator") (part "L7815CP"))
    )
    (comp (ref "U17")
      (value "L7915CV")
      (footprint "TO220V")
      (description "Negative Voltage Regulator")
      (fields (field (name "PUBLISHER") "Altium Limited"))
      (libsource (lib "ST Power Mgt Voltage Regulator") (part "L7915CV"))
    )
    (comp (ref "VCA_IN")
      (value "Header 9")
      (footprint "HDR1X9")
      (description "Header, 9-Pin")
      (fields (field (name "PUBLISHER") "Altium Limited"))
      (libsource (lib "Miscellaneous Connectors") (part "Header 9"))
    )
  )
  (nets
    (net (code "1") (name "+15") (class "Default")
      (node (ref "C12") (pin "1") (pinfunction "1_1") (pintype "passive"))
      (node (ref "C4") (pin "1") (pinfunction "1_1") (pintype "passive"))
      (node (ref "D12") (pin "2") (pinfunction "K_2") (pintype "passive"))
      (node (ref "DEPTH") (pin "1") (pinfunction "1_1") (pintype "passive"))
      (node (ref "MANUAL") (pin "3") (pinfunction "3_3") (pintype "passive"))
      (node (ref "PWR") (pin "3") (pinfunction "3_3") (pintype "passive"))
      (node (ref "R27") (pin "2") (pinfunction "2_2") (pintype "passive"))
      (node (ref "R28") (pin "2") (pinfunction "2_2") (pintype "passive"))
      (node (ref "R29") (pin "2") (pinfunction "2_2") (pintype "passive"))
      (node (ref "R30") (pin "2") (pinfunction "2_2") (pintype "passive"))
      (node (ref "R31") (pin "2") (pinfunction "2_2") (pintype "passive"))
      (node (ref "R32") (pin "2") (pinfunction "2_2") (pintype "passive"))
      (node (ref "R33") (pin "2") (pinfunction "2_2") (pintype "passive"))
      (node (ref "R34") (pin "2") (pinfunction "2_2") (pintype "passive"))
      (node (ref "R35") (pin "2") (pinfunction "2_2") (pintype "passive"))
      (node (ref "R48") (pin "2") (pinfunction "2_2") (pintype "passive"))
      (node (ref "R91") (pin "1") (pinfunction "TOP_1") (pintype "passive"))
      (node (ref "R93") (pin "1") (pinfunction "1_1") (pintype "passive"))
      (node (ref "R95") (pin "2") (pinfunction "2_2") (pintype "passive"))
      (node (ref "U10") (pin "7") (pinfunction "V+_7") (pintype "power_in"))
      (node (ref "U13") (pin "8") (pinfunction "V+_8") (pintype "power_in"))
      (node (ref "U14") (pin "11") (pinfunction "V+_11") (pintype "power_in"))
      (node (ref "U15") (pin "8") (pinfunction "V+_8") (pintype "power_in"))
      (node (ref "U16") (pin "2") (pinfunction "OUT_2") (pintype "power_in"))
    )
    (net (code "2") (name "-6") (class "Default")
      (node (ref "C9") (pin "2") (pinfunction "2_2") (pintype "passive"))
      (node (ref "Q21") (pin "2") (pinfunction "B_2") (pintype "passive"))
      (node (ref "R23") (pin "2") (pinfunction "2_2") (pintype "passive"))
      (node (ref "R24") (pin "2") (pinfunction "2_2") (pintype "passive"))
      (node (ref "R25") (pin "1") (pinfunction "1_1") (pintype "passive"))
      (node (ref "R73") (pin "1") (pinfunction "1_1") (pintype "passive"))
      (node (ref "U11") (pin "2") (pinfunction "A_2") (pintype "power_in"))
      (node (ref "U12") (pin "5") (pinfunction "IN+_5") (pintype "input"))
    )
    (net (code "3") (name "-13") (class "Default")
      (node (ref "Q28") (pin "1") (pinfunction "C_1") (pintype "passive"))
      (node (ref "R76") (pin "2") (pinfunction "2_2") (pintype "passive"))
      (node (ref "U12") (pin "10") (pinfunction "IN+_10") (pintype "input"))
      (node (ref "U12") (pin "12") (pinfunction "IN+_12") (pintype "input"))
      (node (ref "U12") (pin "3") (pinfunction "IN+_3") (pintype "input"))
    )
    (net (code "4") (name "-15") (class "Default")
      (node (ref "C13") (pin "2") (pinfunction "2_2") (pintype "passive"))
      (node (ref "C3") (pin "2") (pinfunction "2_2") (pintype "passive"))
      (node (ref "D11") (pin "1") (pinfunction "A_1") (pintype "passive"))
      (node (ref "MANUAL") (pin "1") (pinfunction "1_1") (pintype "passive"))
      (node (ref "PWR") (pin "1") (pinfunction "1_1") (pintype "passive"))
      (node (ref "Q1") (pin "1") (pinfunction "C_1") (pintype "passive"))
      (node (ref "Q10") (pin "1") (pinfunction "C_1") (pintype "passive"))
      (node (ref "Q12") (pin "1") (pinfunction "C_1") (pintype "passive"))
      (node (ref "Q13") (pin "1") (pinfunction "C_1") (pintype "passive"))
      (node (ref "Q15") (pin "1") (pinfunction "C_1") (pintype "passive"))
      (node (ref "Q16") (pin "1") (pinfunction "C_1") (pintype "passive"))
      (node (ref "Q18") (pin "1") (pinfunction "C_1") (pintype "passive"))
      (node (ref "Q19") (pin "1") (pinfunction "C_1") (pintype "passive"))
      (node (ref "Q21") (pin "1") (pinfunction "C_1") (pintype "passive"))
      (node (ref "Q22") (pin "1") (pinfunction "C_1") (pintype "passive"))
      (node (ref "Q24") (pin "1") (pinfunction "C_1") (pintype "passive"))
      (node (ref "Q3") (pin "1") (pinfunction "C_1") (pintype "passive"))
      (node (ref "Q32") (pin "1") (pinfunction "C_1") (pintype "passive"))
      (node (ref "Q4") (pin "1") (pinfunction "C_1") (pintype "passive"))
      (node (ref "Q6") (pin "1") (pinfunction "C_1") (pintype "passive"))
      (node (ref "Q7") (pin "1") (pinfunction "C_1") (pintype "passive"))
      (node (ref "Q9") (pin "1") (pinfunction "C_1") (pintype "passive"))
      (node (ref "R24") (pin "1") (pinfunction "1_1") (pintype "passive"))
      (node (ref "R76") (pin "1") (pinfunction "1_1") (pintype "passive"))
      (node (ref "R77") (pin "1") (pinfunction "1_1") (pintype "passive"))
      (node (ref "R78") (pin "1") (pinfunction "1_1") (pintype "passive"))
      (node (ref "R79") (pin "1") (pinfunction "1_1") (pintype "passive"))
      (node (ref "R91") (pin "2") (pinfunction "BOT_2") (pintype "passive"))
      (node (ref "RATE") (pin "1") (pinfunction "1_1") (pintype "passive"))
      (node (ref "U10") (pin "4") (pinfunction "V-_4") (pintype "power_in"))
      (node (ref "U12") (pin "11") (pinfunction "V-_11") (pintype "power_in"))
      (node (ref "U13") (pin "4") (pinfunction "V-_4") (pintype "power_in"))
      (node (ref "U14") (pin "10") (pinfunction "BUF_IN2_10") (pintype "passive"))
      (node (ref "U14") (pin "6") (pinfunction "V-_6") (pintype "power_in"))
      (node (ref "U14") (pin "7") (pinfunction "BUF_IN1_7") (pintype "passive"))
      (node (ref "U15") (pin "4") (pinfunction "V-_4") (pintype "power_in"))
      (node (ref "U17") (pin "2") (pinfunction "OUT_2") (pintype "power_in"))
    )
    (net (code "5") (name "GND") (class "Default")
      (node (ref "AC") (pin "2") (pinfunction "2_2") (pintype "passive"))
      (node (ref "AC") (pin "4") (pinfunction "4_4") (pintype "passive"))
      (node (ref "C1") (pin "1") (pinfunction "1_1") (pintype "passive"))
      (node (ref "C11") (pin "2") (pinfunction "2_2") (pintype "passive"))
      (node (ref "C12") (pin "2") (pinfunction "2_2") (pintype "passive"))
      (node (ref "C13") (pin "1") (pinfunction "1_1") (pintype "passive"))
      (node (ref "C2") (pin "2") (pinfunction "2_2") (pintype "passive"))
      (node (ref "C3") (pin "1") (pinfunction "1_1") (pintype "passive"))
      (node (ref "C4") (pin "2") (pinfunction "2_2") (pintype "passive"))
      (node (ref "C6") (pin "2") (pinfunction "2_2") (pintype "passive"))
      (node (ref "C7") (pin "1") (pinfunction "1_1") (pintype "passive"))
      (node (ref "C9") (pin "1") (pinfunction "1_1") (pintype "passive"))
      (node (ref "D10") (pin "2") (pinfunction "K_2") (pintype "passive"))
      (node (ref "D11") (pin "2") (pinfunction "K_2") (pintype "passive"))
      (node (ref "D12") (pin "1") (pinfunction "A_1") (pintype "passive"))
      (node (ref "DEPTH") (pin "3") (pinfunction "3_3") (pintype "passive"))
      (node (ref "DEPTH_CV") (pin "2") (pinfunction "2_2") (pintype "passive"))
      (node (ref "LAG") (pin "2") (pinfunction "2_2") (pintype "passive"))
      (node (ref "OUT") (pin "2") (pinfunction "2_2") (pintype "passive"))
      (node (ref "PWR") (pin "2") (pinfunction "2_2") (pintype "passive"))
      (node (ref "Q30") (pin "2") (pinfunction "B_2") (pintype "passive"))
      (node (ref "Q31") (pin "2") (pinfunction "B_2") (pintype "passive"))
      (node (ref "R26") (pin "2") (pinfunction "2_2") (pintype "passive"))
      (node (ref "R50") (pin "1") (pinfunction "1_1") (pintype "passive"))
      (node (ref "R52") (pin "1") (pinfunction "1_1") (pintype "passive"))
      (node (ref "R53") (pin "1") (pinfunction "1_1") (pintype "passive"))
      (node (ref "R54") (pin "1") (pinfunction "1_1") (pintype "passive"))
      (node (ref "R55") (pin "1") (pinfunction "1_1") (pintype "passive"))
      (node (ref "R56") (pin "1") (pinfunction "1_1") (pintype "passive"))
      (node (ref "R57") (pin "1") (pinfunction "1_1") (pintype "passive"))
      (node (ref "R58") (pin "1") (pinfunction "1_1") (pintype "passive"))
      (node (ref "R59") (pin "1") (pinfunction "1_1") (pintype "passive"))
      (node (ref "R60") (pin "1") (pinfunction "1_1") (pintype "passive"))
      (node (ref "R61") (pin "1") (pinfunction "1_1") (pintype "passive"))
      (node (ref "R62") (pin "1") (pinfunction "1_1") (pintype "passive"))
      (node (ref "R63") (pin "1") (pinfunction "1_1") (pintype "passive"))
      (node (ref "R64") (pin "1") (pinfunction "1_1") (pintype "passive"))
      (node (ref "R65") (pin "1") (pinfunction "1_1") (pintype "passive"))
      (node (ref "R66") (pin "1") (pinfunction "1_1") (pintype "passive"))
      (node (ref "R67") (pin "1") (pinfunction "1_1") (pintype "passive"))
      (node (ref "R68") (pin "1") (pinfunction "1_1") (pintype "passive"))
      (node (ref "R69") (pin "1") (pinfunction "1_1") (pintype "passive"))
      (node (ref "R72") (pin "2") (pinfunction "2_2") (pintype "passive"))
      (node (ref "R75") (pin "2") (pinfunction "2_2") (pintype "passive"))
      (node (ref "R82") (pin "1") (pinfunction "1_1") (pintype "passive"))
      (node (ref "R86") (pin "2") (pinfunction "2_2") (pintype "passive"))
      (node (ref "R92") (pin "1") (pinfunction "1_1") (pintype "passive"))
      (node (ref "RATE") (pin "3") (pinfunction "3_3") (pintype "passive"))
      (node (ref "RATE_CV") (pin "2") (pinfunction "2_2") (pintype "passive"))
      (node (ref "SCAN_CV") (pin "2") (pinfunction "2_2") (pintype "passive"))
      (node (ref "U11") (pin "3") (pinfunction "K_3") (pintype "power_in"))
      (node (ref "U12") (pin "4") (pinfunction "V+_4") (pintype "power_in"))
      (node (ref "U13") (pin "5") (pinfunction "IN+_5") (pintype "input"))
      (node (ref "U14") (pin "13") (pinfunction "IN2-_13") (pintype "input"))
      (node (ref "U14") (pin "4") (pinfunction "IN1-_4") (pintype "input"))
      (node (ref "U15") (pin "2") (pinfunction "IN-_2") (pintype "input"))
      (node (ref "U15") (pin "5") (pinfunction "IN+_5") (pintype "input"))
      (node (ref "U16") (pin "3") (pinfunction "GND_3") (pintype "power_in"))
      (node (ref "U17") (pin "1") (pinfunction "GND_1") (pintype "power_in"))
    )
    (net (code "6") (name "Net-(AC-Pad1)") (class "Default")
      (node (ref "AC") (pin "1") (pinfunction "1_1") (pintype "passive"))
      (node (ref "BRIDGE") (pin "2") (pinfunction "AC_2") (pintype "passive"))
    )
    (net (code "7") (name "Net-(AC-Pad5)") (class "Default")
      (node (ref "AC") (pin "5") (pinfunction "5_5") (pintype "passive"))
      (node (ref "BRIDGE") (pin "4") (pinfunction "AC_4") (pintype "passive"))
    )
    (net (code "8") (name "Net-(BRIDGE-V+)") (class "Default")
      (node (ref "BRIDGE") (pin "1") (pinfunction "V+_1") (pintype "passive"))
      (node (ref "C2") (pin "1") (pinfunction "1_1") (pintype "passive"))
      (node (ref "U16") (pin "1") (pinfunction "IN_1") (pintype "power_in"))
    )
    (net (code "9") (name "Net-(BRIDGE-V-)") (class "Default")
      (node (ref "BRIDGE") (pin "3") (pinfunction "V-_3") (pintype "passive"))
      (node (ref "C1") (pin "2") (pinfunction "2_2") (pintype "passive"))
      (node (ref "U17") (pin "3") (pinfunction "IN_3") (pintype "power_in"))
    )
    (net (code "10") (name "Net-(C5-Pad1)") (class "Default")
      (node (ref "C5") (pin "1") (pinfunction "1_1") (pintype "passive"))
      (node (ref "LAG") (pin "1") (pinfunction "1_1") (pintype "passive"))
    )
    (net (code "11") (name "Net-(C11-Pad1)") (class "Default")
      (node (ref "C11") (pin "1") (pinfunction "1_1") (pintype "passive"))
      (node (ref "MANUAL") (pin "2") (pinfunction "2_2") (pintype "passive"))
      (node (ref "R80") (pin "1") (pinfunction "1_1") (pintype "passive"))
    )
    (net (code "12") (name "Net-(D1-A)") (class "Default")
      (node (ref "D1") (pin "1") (pinfunction "A_1") (pintype "passive"))
      (node (ref "U1") (pin "3") (pinfunction "E_3") (pintype "passive"))
      (node (ref "U1") (pin "4") (pinfunction "E_4") (pintype "passive"))
    )
    (net (code "13") (name "Net-(D1-K)") (class "Default")
      (node (ref "D1") (pin "2") (pinfunction "K_2") (pintype "passive"))
      (node (ref "Q2") (pin "1") (pinfunction "C_1") (pintype "passive"))
    )
    (net (code "14") (name "Net-(D2-A)") (class "Default")
      (node (ref "D2") (pin "1") (pinfunction "A_1") (pintype "passive"))
      (node (ref "U2") (pin "3") (pinfunction "E_3") (pintype "passive"))
      (node (ref "U2") (pin "4") (pinfunction "E_4") (pintype "passive"))
    )
    (net (code "15") (name "Net-(D2-K)") (class "Default")
      (node (ref "D2") (pin "2") (pinfunction "K_2") (pintype "passive"))
      (node (ref "Q5") (pin "1") (pinfunction "C_1") (pintype "passive"))
    )
    (net (code "16") (name "Net-(D3-A)") (class "Default")
      (node (ref "D3") (pin "1") (pinfunction "A_1") (pintype "passive"))
      (node (ref "U3") (pin "3") (pinfunction "E_3") (pintype "passive"))
      (node (ref "U3") (pin "4") (pinfunction "E_4") (pintype "passive"))
    )
    (net (code "17") (name "Net-(D3-K)") (class "Default")
      (node (ref "D3") (pin "2") (pinfunction "K_2") (pintype "passive"))
      (node (ref "Q8") (pin "1") (pinfunction "C_1") (pintype "passive"))
    )
    (net (code "18") (name "Net-(D4-A)") (class "Default")
      (node (ref "D4") (pin "1") (pinfunction "A_1") (pintype "passive"))
      (node (ref "U4") (pin "3") (pinfunction "E_3") (pintype "passive"))
      (node (ref "U4") (pin "4") (pinfunction "E_4") (pintype "passive"))
    )
    (net (code "19") (name "Net-(D4-K)") (class "Default")
      (node (ref "D4") (pin "2") (pinfunction "K_2") (pintype "passive"))
      (node (ref "Q11") (pin "1") (pinfunction "C_1") (pintype "passive"))
    )
    (net (code "20") (name "Net-(D5-A)") (class "Default")
      (node (ref "D5") (pin "1") (pinfunction "A_1") (pintype "passive"))
      (node (ref "U5") (pin "3") (pinfunction "E_3") (pintype "passive"))
      (node (ref "U5") (pin "4") (pinfunction "E_4") (pintype "passive"))
    )
    (net (code "21") (name "Net-(D5-K)") (class "Default")
      (node (ref "D5") (pin "2") (pinfunction "K_2") (pintype "passive"))
      (node (ref "Q14") (pin "1") (pinfunction "C_1") (pintype "passive"))
    )
    (net (code "22") (name "Net-(D6-A)") (class "Default")
      (node (ref "D6") (pin "1") (pinfunction "A_1") (pintype "passive"))
      (node (ref "U6") (pin "3") (pinfunction "E_3") (pintype "passive"))
      (node (ref "U6") (pin "4") (pinfunction "E_4") (pintype "passive"))
    )
    (net (code "23") (name "Net-(D6-K)") (class "Default")
      (node (ref "D6") (pin "2") (pinfunction "K_2") (pintype "passive"))
      (node (ref "Q17") (pin "1") (pinfunction "C_1") (pintype "passive"))
    )
    (net (code "24") (name "Net-(D7-A)") (class "Default")
      (node (ref "D7") (pin "1") (pinfunction "A_1") (pintype "passive"))
      (node (ref "U7") (pin "3") (pinfunction "E_3") (pintype "passive"))
      (node (ref "U7") (pin "4") (pinfunction "E_4") (pintype "passive"))
    )
    (net (code "25") (name "Net-(D7-K)") (class "Default")
      (node (ref "D7") (pin "2") (pinfunction "K_2") (pintype "passive"))
      (node (ref "Q20") (pin "1") (pinfunction "C_1") (pintype "passive"))
    )
    (net (code "26") (name "Net-(D8-A)") (class "Default")
      (node (ref "D8") (pin "1") (pinfunction "A_1") (pintype "passive"))
      (node (ref "U8") (pin "3") (pinfunction "E_3") (pintype "passive"))
      (node (ref "U8") (pin "4") (pinfunction "E_4") (pintype "passive"))
    )
    (net (code "27") (name "Net-(D8-K)") (class "Default")
      (node (ref "D8") (pin "2") (pinfunction "K_2") (pintype "passive"))
      (node (ref "Q23") (pin "1") (pinfunction "C_1") (pintype "passive"))
    )
    (net (code "28") (name "Net-(D9-A)") (class "Default")
      (node (ref "D9") (pin "1") (pinfunction "A_1") (pintype "passive"))
      (node (ref "U9") (pin "3") (pinfunction "E_3") (pintype "passive"))
      (node (ref "U9") (pin "4") (pinfunction "E_4") (pintype "passive"))
    )
    (net (code "29") (name "Net-(D9-K)") (class "Default")
      (node (ref "D9") (pin "2") (pinfunction "K_2") (pintype "passive"))
      (node (ref "Q25") (pin "1") (pinfunction "C_1") (pintype "passive"))
    )
    (net (code "30") (name "Net-(D10-A)") (class "Default")
      (node (ref "C5") (pin "2") (pinfunction "2_2") (pintype "passive"))
      (node (ref "D10") (pin "1") (pinfunction "A_1") (pintype "passive"))
      (node (ref "R96") (pin "1") (pinfunction "1_1") (pintype "passive"))
      (node (ref "R97") (pin "2") (pinfunction "2_2") (pintype "passive"))
    )
    (net (code "31") (name "Net-(DEPTH-Pad2)") (class "Default")
      (node (ref "DEPTH") (pin "2") (pinfunction "2_2") (pintype "passive"))
      (node (ref "R84") (pin "1") (pinfunction "1_1") (pintype "passive"))
    )
    (net (code "32") (name "Net-(DEPTH_CV-Pad1)") (class "Default")
      (node (ref "DEPTH_CV") (pin "1") (pinfunction "1_1") (pintype "passive"))
      (node (ref "R85") (pin "1") (pinfunction "1_1") (pintype "passive"))
    )
    (net (code "33") (name "Net-(OUT-Pad1)") (class "Default")
      (node (ref "OUT") (pin "1") (pinfunction "1_1") (pintype "passive"))
      (node (ref "R51") (pin "1") (pinfunction "1_1") (pintype "passive"))
    )
    (net (code "34") (name "Net-(Q1-B)") (class "Default")
      (node (ref "Q1") (pin "2") (pinfunction "B_2") (pintype "passive"))
      (node (ref "Q26") (pin "1") (pinfunction "C_1") (pintype "passive"))
      (node (ref "R17") (pin "1") (pinfunction "1_1") (pintype "passive"))
    )
    (net (code "35") (name "Net-(Q1-E)") (class "Default")
      (node (ref "Q1") (pin "3") (pinfunction "E_3") (pintype "passive"))
      (node (ref "Q2") (pin "2") (pinfunction "B_2") (pintype "passive"))
      (node (ref "R27") (pin "1") (pinfunction "1_1") (pintype "passive"))
    )
    (net (code "36") (name "Net-(Q2-E)") (class "Default")
      (node (ref "Q2") (pin "3") (pinfunction "E_3") (pintype "passive"))
      (node (ref "R1") (pin "2") (pinfunction "2_2") (pintype "passive"))
    )
    (net (code "37") (name "Net-(Q3-B)") (class "Default")
      (node (ref "Q3") (pin "2") (pinfunction "B_2") (pintype "passive"))
      (node (ref "R17") (pin "2") (pinfunction "2_2") (pintype "passive"))
      (node (ref "R18") (pin "1") (pinfunction "1_1") (pintype "passive"))
    )
    (net (code "38") (name "Net-(Q3-E)") (class "Default")
      (node (ref "Q3") (pin "3") (pinfunction "E_3") (pintype "passive"))
      (node (ref "Q4") (pin "3") (pinfunction "E_3") (pintype "passive"))
      (node (ref "Q5") (pin "2") (pinfunction "B_2") (pintype "passive"))
      (node (ref "R28") (pin "1") (pinfunction "1_1") (pintype "passive"))
    )
    (net (code "39") (name "Net-(Q4-B)") (class "Default")
      (node (ref "Q4") (pin "2") (pinfunction "B_2") (pintype "passive"))
      (node (ref "R10") (pin "1") (pinfunction "1_1") (pintype "passive"))
      (node (ref "R70") (pin "2") (pinfunction "2_2") (pintype "passive"))
      (node (ref "U13") (pin "1") (pinfunction "OUT_1") (pintype "output"))
    )
    (net (code "40") (name "Net-(Q5-E)") (class "Default")
      (node (ref "Q5") (pin "3") (pinfunction "E_3") (pintype "passive"))
      (node (ref "R2") (pin "2") (pinfunction "2_2") (pintype "passive"))
    )
    (net (code "41") (name "Net-(Q6-B)") (class "Default")
      (node (ref "Q6") (pin "2") (pinfunction "B_2") (pintype "passive"))
      (node (ref "R18") (pin "2") (pinfunction "2_2") (pintype "passive"))
      (node (ref "R19") (pin "1") (pinfunction "1_1") (pintype "passive"))
    )
    (net (code "42") (name "Net-(Q6-E)") (class "Default")
      (node (ref "Q6") (pin "3") (pinfunction "E_3") (pintype "passive"))
      (node (ref "Q7") (pin "3") (pinfunction "E_3") (pintype "passive"))
      (node (ref "Q8") (pin "2") (pinfunction "B_2") (pintype "passive"))
      (node (ref "R29") (pin "1") (pinfunction "1_1") (pintype "passive"))
    )
    (net (code "43") (name "Net-(Q7-B)") (class "Default")
      (node (ref "Q7") (pin "2") (pinfunction "B_2") (pintype "passive"))
      (node (ref "R10") (pin "2") (pinfunction "2_2") (pintype "passive"))
      (node (ref "R11") (pin "1") (pinfunction "1_1") (pintype "passive"))
    )
    (net (code "44") (name "Net-(Q8-E)") (class "Default")
      (node (ref "Q8") (pin "3") (pinfunction "E_3") (pintype "passive"))
      (node (ref "R3") (pin "2") (pinfunction "2_2") (pintype "passive"))
    )
    (net (code "45") (name "Net-(Q9-B)") (class "Default")
      (node (ref "Q9") (pin "2") (pinfunction "B_2") (pintype "passive"))
      (node (ref "R19") (pin "2") (pinfunction "2_2") (pintype "passive"))
      (node (ref "R20") (pin "1") (pinfunction "1_1") (pintype "passive"))
    )
    (net (code "46") (name "Net-(Q10-B)") (class "Default")
      (node (ref "Q10") (pin "2") (pinfunction "B_2") (pintype "passive"))
      (node (ref "R11") (pin "2") (pinfunction "2_2") (pintype "passive"))
      (node (ref "R12") (pin "1") (pinfunction "1_1") (pintype "passive"))
    )
    (net (code "47") (name "Net-(Q10-E)") (class "Default")
      (node (ref "Q10") (pin "3") (pinfunction "E_3") (pintype "passive"))
      (node (ref "Q11") (pin "2") (pinfunction "B_2") (pintype "passive"))
      (node (ref "Q9") (pin "3") (pinfunction "E_3") (pintype "passive"))
      (node (ref "R30") (pin "1") (pinfunction "1_1") (pintype "passive"))
    )
    (net (code "48") (name "Net-(Q11-E)") (class "Default")
      (node (ref "Q11") (pin "3") (pinfunction "E_3") (pintype "passive"))
      (node (ref "R4") (pin "2") (pinfunction "2_2") (pintype "passive"))
    )
    (net (code "49") (name "Net-(Q12-B)") (class "Default")
      (node (ref "Q12") (pin "2") (pinfunction "B_2") (pintype "passive"))
      (node (ref "R20") (pin "2") (pinfunction "2_2") (pintype "passive"))
      (node (ref "R21") (pin "1") (pinfunction "1_1") (pintype "passive"))
    )
    (net (code "50") (name "Net-(Q12-E)") (class "Default")
      (node (ref "Q12") (pin "3") (pinfunction "E_3") (pintype "passive"))
      (node (ref "Q13") (pin "3") (pinfunction "E_3") (pintype "passive"))
      (node (ref "Q14") (pin "2") (pinfunction "B_2") (pintype "passive"))
      (node (ref "R31") (pin "1") (pinfunction "1_1") (pintype "passive"))
    )
    (net (code "51") (name "Net-(Q13-B)") (class "Default")
      (node (ref "Q13") (pin "2") (pinfunction "B_2") (pintype "passive"))
      (node (ref "R12") (pin "2") (pinfunction "2_2") (pintype "passive"))
      (node (ref "R13") (pin "1") (pinfunction "1_1") (pintype "passive"))
    )
    (net (code "52") (name "Net-(Q14-E)") (class "Default")
      (node (ref "Q14") (pin "3") (pinfunction "E_3") (pintype "passive"))
      (node (ref "R5") (pin "2") (pinfunction "2_2") (pintype "passive"))
    )
    (net (code "53") (name "Net-(Q15-B)") (class "Default")
      (node (ref "Q15") (pin "2") (pinfunction "B_2") (pintype "passive"))
      (node (ref "R21") (pin "2") (pinfunction "2_2") (pintype "passive"))
      (node (ref "R22") (pin "1") (pinfunction "1_1") (pintype "passive"))
    )
    (net (code "54") (name "Net-(Q15-E)") (class "Default")
      (node (ref "Q15") (pin "3") (pinfunction "E_3") (pintype "passive"))
      (node (ref "Q16") (pin "3") (pinfunction "E_3") (pintype "passive"))
      (node (ref "Q17") (pin "2") (pinfunction "B_2") (pintype "passive"))
      (node (ref "R32") (pin "1") (pinfunction "1_1") (pintype "passive"))
    )
    (net (code "55") (name "Net-(Q16-B)") (class "Default")
      (node (ref "Q16") (pin "2") (pinfunction "B_2") (pintype "passive"))
      (node (ref "R13") (pin "2") (pinfunction "2_2") (pintype "passive"))
      (node (ref "R14") (pin "1") (pinfunction "1_1") (pintype "passive"))
    )
    (net (code "56") (name "Net-(Q17-E)") (class "Default")
      (node (ref "Q17") (pin "3") (pinfunction "E_3") (pintype "passive"))
      (node (ref "R6") (pin "2") (pinfunction "2_2") (pintype "passive"))
    )
    (net (code "57") (name "Net-(Q18-B)") (class "Default")
      (node (ref "Q18") (pin "2") (pinfunction "B_2") (pintype "passive"))
      (node (ref "R22") (pin "2") (pinfunction "2_2") (pintype "passive"))
      (node (ref "R23") (pin "1") (pinfunction "1_1") (pintype "passive"))
    )
    (net (code "58") (name "Net-(Q18-E)") (class "Default")
      (node (ref "Q18") (pin "3") (pinfunction "E_3") (pintype "passive"))
      (node (ref "Q19") (pin "3") (pinfunction "E_3") (pintype "passive"))
      (node (ref "Q20") (pin "2") (pinfunction "B_2") (pintype "passive"))
      (node (ref "R33") (pin "1") (pinfunction "1_1") (pintype "passive"))
    )
    (net (code "59") (name "Net-(Q19-B)") (class "Default")
      (node (ref "Q19") (pin "2") (pinfunction "B_2") (pintype "passive"))
      (node (ref "R14") (pin "2") (pinfunction "2_2") (pintype "passive"))
      (node (ref "R15") (pin "1") (pinfunction "1_1") (pintype "passive"))
    )
    (net (code "60") (name "Net-(Q20-E)") (class "Default")
      (node (ref "Q20") (pin "3") (pinfunction "E_3") (pintype "passive"))
      (node (ref "R7") (pin "2") (pinfunction "2_2") (pintype "passive"))
    )
    (net (code "61") (name "Net-(Q21-E)") (class "Default")
      (node (ref "Q21") (pin "3") (pinfunction "E_3") (pintype "passive"))
      (node (ref "Q22") (pin "3") (pinfunction "E_3") (pintype "passive"))
      (node (ref "Q23") (pin "2") (pinfunction "B_2") (pintype "passive"))
      (node (ref "R34") (pin "1") (pinfunction "1_1") (pintype "passive"))
    )
    (net (code "62") (name "Net-(Q22-B)") (class "Default")
      (node (ref "Q22") (pin "2") (pinfunction "B_2") (pintype "passive"))
      (node (ref "R15") (pin "2") (pinfunction "2_2") (pintype "passive"))
      (node (ref "R16") (pin "1") (pinfunction "1_1") (pintype "passive"))
    )
    (net (code "63") (name "Net-(Q23-E)") (class "Default")
      (node (ref "Q23") (pin "3") (pinfunction "E_3") (pintype "passive"))
      (node (ref "R8") (pin "2") (pinfunction "2_2") (pintype "passive"))
    )
    (net (code "64") (name "Net-(Q24-B)") (class "Default")
      (node (ref "Q24") (pin "2") (pinfunction "B_2") (pintype "passive"))
      (node (ref "Q29") (pin "1") (pinfunction "C_1") (pintype "passive"))
      (node (ref "R16") (pin "2") (pinfunction "2_2") (pintype "passive"))
    )
    (net (code "65") (name "Net-(Q24-E)") (class "Default")
      (node (ref "Q24") (pin "3") (pinfunction "E_3") (pintype "passive"))
      (node (ref "Q25") (pin "2") (pinfunction "B_2") (pintype "passive"))
      (node (ref "R35") (pin "1") (pinfunction "1_1") (pintype "passive"))
    )
    (net (code "66") (name "Net-(Q25-E)") (class "Default")
      (node (ref "Q25") (pin "3") (pinfunction "E_3") (pintype "passive"))
      (node (ref "R9") (pin "2") (pinfunction "2_2") (pintype "passive"))
    )
    (net (code "67") (name "Net-(Q26-B)") (class "Default")
      (node (ref "Q26") (pin "2") (pinfunction "B_2") (pintype "passive"))
      (node (ref "U12") (pin "14") (pinfunction "OUT_14") (pintype "output"))
    )
    (net (code "68") (name "Net-(Q26-E)") (class "Default")
      (node (ref "Q26") (pin "3") (pinfunction "E_3") (pintype "passive"))
      (node (ref "R78") (pin "2") (pinfunction "2_2") (pintype "passive"))
      (node (ref "U12") (pin "13") (pinfunction "IN-_13") (pintype "input"))
    )
    (net (code "69") (name "Net-(Q27-B)") (class "Default")
      (node (ref "Q27") (pin "2") (pinfunction "B_2") (pintype "passive"))
      (node (ref "U12") (pin "1") (pinfunction "OUT_1") (pintype "output"))
    )
    (net (code "70") (name "Net-(Q27-C)") (class "Default")
      (node (ref "Q27") (pin "1") (pinfunction "C_1") (pintype "passive"))
      (node (ref "R1") (pin "1") (pinfunction "1_1") (pintype "passive"))
      (node (ref "R2") (pin "1") (pinfunction "1_1") (pintype "passive"))
      (node (ref "R3") (pin "1") (pinfunction "1_1") (pintype "passive"))
      (node (ref "R4") (pin "1") (pinfunction "1_1") (pintype "passive"))
      (node (ref "R5") (pin "1") (pinfunction "1_1") (pintype "passive"))
      (node (ref "R6") (pin "1") (pinfunction "1_1") (pintype "passive"))
      (node (ref "R7") (pin "1") (pinfunction "1_1") (pintype "passive"))
      (node (ref "R8") (pin "1") (pinfunction "1_1") (pintype "passive"))
      (node (ref "R9") (pin "1") (pinfunction "1_1") (pintype "passive"))
    )
    (net (code "71") (name "Net-(Q27-E)") (class "Default")
      (node (ref "Q27") (pin "3") (pinfunction "E_3") (pintype "passive"))
      (node (ref "R79") (pin "2") (pinfunction "2_2") (pintype "passive"))
      (node (ref "U12") (pin "2") (pinfunction "IN-_2") (pintype "input"))
    )
    (net (code "72") (name "Net-(Q28-B)") (class "Default")
      (node (ref "Q28") (pin "2") (pinfunction "B_2") (pintype "passive"))
      (node (ref "U12") (pin "7") (pinfunction "OUT_7") (pintype "output"))
    )
    (net (code "73") (name "Net-(Q28-E)") (class "Default")
      (node (ref "Q28") (pin "3") (pinfunction "E_3") (pintype "passive"))
      (node (ref "R75") (pin "1") (pinfunction "1_1") (pintype "passive"))
      (node (ref "U12") (pin "6") (pinfunction "IN-_6") (pintype "input"))
    )
    (net (code "74") (name "Net-(Q29-B)") (class "Default")
      (node (ref "Q29") (pin "2") (pinfunction "B_2") (pintype "passive"))
      (node (ref "U12") (pin "8") (pinfunction "OUT_8") (pintype "output"))
    )
    (net (code "75") (name "Net-(Q29-E)") (class "Default")
      (node (ref "Q29") (pin "3") (pinfunction "E_3") (pintype "passive"))
      (node (ref "R77") (pin "2") (pinfunction "2_2") (pintype "passive"))
      (node (ref "U12") (pin "9") (pinfunction "IN-_9") (pintype "input"))
    )
    (net (code "76") (name "Net-(Q30-C)") (class "Default")
      (node (ref "Q30") (pin "1") (pinfunction "C_1") (pintype "passive"))
      (node (ref "U14") (pin "16") (pinfunction "AMP_BIAS_IN2_16") (pintype "passive"))
    )
    (net (code "77") (name "Net-(Q30-E)") (class "Default")
      (node (ref "Q30") (pin "3") (pinfunction "E_3") (pintype "passive"))
      (node (ref "R84") (pin "2") (pinfunction "2_2") (pintype "passive"))
      (node (ref "R85") (pin "2") (pinfunction "2_2") (pintype "passive"))
    )
    (net (code "78") (name "Net-(Q31-C)") (class "Default")
      (node (ref "Q31") (pin "1") (pinfunction "C_1") (pintype "passive"))
      (node (ref "U14") (pin "1") (pinfunction "AMP_BIAS_IN1_1") (pintype "passive"))
    )
    (net (code "79") (name "Net-(Q31-E)") (class "Default")
      (node (ref "Q31") (pin "3") (pinfunction "E_3") (pintype "passive"))
      (node (ref "Q32") (pin "3") (pinfunction "E_3") (pintype "passive"))
      (node (ref "R93") (pin "2") (pinfunction "2_2") (pintype "passive"))
    )
    (net (code "80") (name "Net-(Q32-B)") (class "Default")
      (node (ref "Q32") (pin "2") (pinfunction "B_2") (pintype "passive"))
      (node (ref "R92") (pin "2") (pinfunction "2_2") (pintype "passive"))
      (node (ref "R94") (pin "2") (pinfunction "2_2") (pintype "passive"))
      (node (ref "R96") (pin "2") (pinfunction "2_2") (pintype "passive"))
    )
    (net (code "81") (name "Net-(R36-Pad1)") (class "Default")
      (node (ref "R36") (pin "1") (pinfunction "1_1") (pintype "passive"))
      (node (ref "R52") (pin "2") (pinfunction "2_2") (pintype "passive"))
      (node (ref "U1") (pin "2") (pinfunction "B_2") (pintype "passive"))
    )
    (net (code "82") (name "Net-(R36-Pad2)") (class "Default")
      (node (ref "R36") (pin "2") (pinfunction "2_2") (pintype "passive"))
      (node (ref "VCA_IN") (pin "1") (pinfunction "1_1") (pintype "passive"))
    )
    (net (code "83") (name "Net-(R37-Pad1)") (class "Default")
      (node (ref "R37") (pin "1") (pinfunction "1_1") (pintype "passive"))
      (node (ref "R54") (pin "2") (pinfunction "2_2") (pintype "passive"))
      (node (ref "U2") (pin "2") (pinfunction "B_2") (pintype "passive"))
    )
    (net (code "84") (name "Net-(R37-Pad2)") (class "Default")
      (node (ref "R37") (pin "2") (pinfunction "2_2") (pintype "passive"))
      (node (ref "VCA_IN") (pin "2") (pinfunction "2_2") (pintype "passive"))
    )
    (net (code "85") (name "Net-(R38-Pad1)") (class "Default")
      (node (ref "R38") (pin "1") (pinfunction "1_1") (pintype "passive"))
      (node (ref "R56") (pin "2") (pinfunction "2_2") (pintype "passive"))
      (node (ref "U3") (pin "2") (pinfunction "B_2") (pintype "passive"))
    )
    (net (code "86") (name "Net-(R38-Pad2)") (class "Default")
      (node (ref "R38") (pin "2") (pinfunction "2_2") (pintype "passive"))
      (node (ref "VCA_IN") (pin "3") (pinfunction "3_3") (pintype "passive"))
    )
    (net (code "87") (name "Net-(R39-Pad1)") (class "Default")
      (node (ref "R39") (pin "1") (pinfunction "1_1") (pintype "passive"))
      (node (ref "R58") (pin "2") (pinfunction "2_2") (pintype "passive"))
      (node (ref "U4") (pin "2") (pinfunction "B_2") (pintype "passive"))
    )
    (net (code "88") (name "Net-(R39-Pad2)") (class "Default")
      (node (ref "R39") (pin "2") (pinfunction "2_2") (pintype "passive"))
      (node (ref "VCA_IN") (pin "4") (pinfunction "4_4") (pintype "passive"))
    )
    (net (code "89") (name "Net-(R40-Pad1)") (class "Default")
      (node (ref "R40") (pin "1") (pinfunction "1_1") (pintype "passive"))
      (node (ref "R60") (pin "2") (pinfunction "2_2") (pintype "passive"))
      (node (ref "U5") (pin "2") (pinfunction "B_2") (pintype "passive"))
    )
    (net (code "90") (name "Net-(R40-Pad2)") (class "Default")
      (node (ref "R40") (pin "2") (pinfunction "2_2") (pintype "passive"))
      (node (ref "VCA_IN") (pin "5") (pinfunction "5_5") (pintype "passive"))
    )
    (net (code "91") (name "Net-(R41-Pad1)") (class "Default")
      (node (ref "R41") (pin "1") (pinfunction "1_1") (pintype "passive"))
      (node (ref "R62") (pin "2") (pinfunction "2_2") (pintype "passive"))
      (node (ref "U6") (pin "2") (pinfunction "B_2") (pintype "passive"))
    )
    (net (code "92") (name "Net-(R41-Pad2)") (class "Default")
      (node (ref "R41") (pin "2") (pinfunction "2_2") (pintype "passive"))
      (node (ref "VCA_IN") (pin "6") (pinfunction "6_6") (pintype "passive"))
    )
    (net (code "93") (name "Net-(R42-Pad1)") (class "Default")
      (node (ref "R42") (pin "1") (pinfunction "1_1") (pintype "passive"))
      (node (ref "R64") (pin "2") (pinfunction "2_2") (pintype "passive"))
      (node (ref "U7") (pin "2") (pinfunction "B_2") (pintype "passive"))
    )
    (net (code "94") (name "Net-(R42-Pad2)") (class "Default")
      (node (ref "R42") (pin "2") (pinfunction "2_2") (pintype "passive"))
      (node (ref "VCA_IN") (pin "7") (pinfunction "7_7") (pintype "passive"))
    )
    (net (code "95") (name "Net-(R43-Pad1)") (class "Default")
      (node (ref "R43") (pin "1") (pinfunction "1_1") (pintype "passive"))
      (node (ref "R66") (pin "2") (pinfunction "2_2") (pintype "passive"))
      (node (ref "U8") (pin "2") (pinfunction "B_2") (pintype "passive"))
    )
    (net (code "96") (name "Net-(R43-Pad2)") (class "Default")
      (node (ref "R43") (pin "2") (pinfunction "2_2") (pintype "passive"))
      (node (ref "VCA_IN") (pin "8") (pinfunction "8_8") (pintype "passive"))
    )
    (net (code "97") (name "Net-(R44-Pad1)") (class "Default")
      (node (ref "R44") (pin "1") (pinfunction "1_1") (pintype "passive"))
      (node (ref "R68") (pin "2") (pinfunction "2_2") (pintype "passive"))
      (node (ref "U9") (pin "2") (pinfunction "B_2") (pintype "passive"))
    )
    (net (code "98") (name "Net-(R44-Pad2)") (class "Default")
      (node (ref "R44") (pin "2") (pinfunction "2_2") (pintype "passive"))
      (node (ref "VCA_IN") (pin "9") (pinfunction "9_9") (pintype "passive"))
    )
    (net (code "99") (name "Net-(R47-BOT)") (class "Default")
      (node (ref "R45") (pin "1") (pinfunction "1_1") (pintype "passive"))
      (node (ref "R47") (pin "2") (pinfunction "BOT_2") (pintype "passive"))
    )
    (net (code "100") (name "Net-(R47-TAP)") (class "Default")
      (node (ref "C6") (pin "1") (pinfunction "1_1") (pintype "passive"))
      (node (ref "R47") (pin "3") (pinfunction "TAP_3") (pintype "passive"))
      (node (ref "R48") (pin "1") (pinfunction "1_1") (pintype "passive"))
    )
    (net (code "101") (name "Net-(R47-TOP)") (class "Default")
      (node (ref "R46") (pin "2") (pinfunction "2_2") (pintype "passive"))
      (node (ref "R47") (pin "1") (pinfunction "TOP_1") (pintype "passive"))
    )
    (net (code "102") (name "Net-(R53-Pad2)") (class "Default")
      (node (ref "R53") (pin "2") (pinfunction "2_2") (pintype "passive"))
      (node (ref "U1") (pin "5") (pinfunction "B_5") (pintype "passive"))
    )
    (net (code "103") (name "Net-(R55-Pad2)") (class "Default")
      (node (ref "R55") (pin "2") (pinfunction "2_2") (pintype "passive"))
      (node (ref "U2") (pin "5") (pinfunction "B_5") (pintype "passive"))
    )
    (net (code "104") (name "Net-(R57-Pad2)") (class "Default")
      (node (ref "R57") (pin "2") (pinfunction "2_2") (pintype "passive"))
      (node (ref "U3") (pin "5") (pinfunction "B_5") (pintype "passive"))
    )
    (net (code "105") (name "Net-(R59-Pad2)") (class "Default")
      (node (ref "R59") (pin "2") (pinfunction "2_2") (pintype "passive"))
      (node (ref "U4") (pin "5") (pinfunction "B_5") (pintype "passive"))
    )
    (net (code "106") (name "Net-(R61-Pad2)") (class "Default")
      (node (ref "R61") (pin "2") (pinfunction "2_2") (pintype "passive"))
      (node (ref "U5") (pin "5") (pinfunction "B_5") (pintype "passive"))
    )
    (net (code "107") (name "Net-(R63-Pad2)") (class "Default")
      (node (ref "R63") (pin "2") (pinfunction "2_2") (pintype "passive"))
      (node (ref "U6") (pin "5") (pinfunction "B_5") (pintype "passive"))
    )
    (net (code "108") (name "Net-(R65-Pad2)") (class "Default")
      (node (ref "R65") (pin "2") (pinfunction "2_2") (pintype "passive"))
      (node (ref "U7") (pin "5") (pinfunction "B_5") (pintype "passive"))
    )
    (net (code "109") (name "Net-(R67-Pad2)") (class "Default")
      (node (ref "R67") (pin "2") (pinfunction "2_2") (pintype "passive"))
      (node (ref "U8") (pin "5") (pinfunction "B_5") (pintype "passive"))
    )
    (net (code "110") (name "Net-(R69-Pad2)") (class "Default")
      (node (ref "R69") (pin "2") (pinfunction "2_2") (pintype "passive"))
      (node (ref "U9") (pin "5") (pinfunction "B_5") (pintype "passive"))
    )
    (net (code "111") (name "Net-(R81-Pad1)") (class "Default")
      (node (ref "R81") (pin "1") (pinfunction "1_1") (pintype "passive"))
      (node (ref "SCAN_CV") (pin "1") (pinfunction "1_1") (pintype "passive"))
    )
    (net (code "112") (name "Net-(R91-TAP)") (class "Default")
      (node (ref "R90") (pin "2") (pinfunction "2_2") (pintype "passive"))
      (node (ref "R91") (pin "3") (pinfunction "TAP_3") (pintype "passive"))
    )
    (net (code "113") (name "Net-(R94-Pad1)") (class "Default")
      (node (ref "R94") (pin "1") (pinfunction "1_1") (pintype "passive"))
      (node (ref "R95") (pin "1") (pinfunction "1_1") (pintype "passive"))
      (node (ref "RATE_CV") (pin "1") (pinfunction "1_1") (pintype "passive"))
    )
    (net (code "114") (name "Net-(R97-Pad1)") (class "Default")
      (node (ref "R97") (pin "1") (pinfunction "1_1") (pintype "passive"))
      (node (ref "RATE") (pin "2") (pinfunction "2_2") (pintype "passive"))
    )
    (net (code "115") (name "Net-(U10-IN+)") (class "Default")
      (node (ref "C7") (pin "2") (pinfunction "2_2") (pintype "passive"))
      (node (ref "R45") (pin "2") (pinfunction "2_2") (pintype "passive"))
      (node (ref "R50") (pin "2") (pinfunction "2_2") (pintype "passive"))
      (node (ref "U1") (pin "6") (pinfunction "C_6") (pintype "passive"))
      (node (ref "U10") (pin "3") (pinfunction "IN+_3") (pintype "input"))
      (node (ref "U2") (pin "6") (pinfunction "C_6") (pintype "passive"))
      (node (ref "U3") (pin "6") (pinfunction "C_6") (pintype "passive"))
      (node (ref "U4") (pin "6") (pinfunction "C_6") (pintype "passive"))
      (node (ref "U5") (pin "6") (pinfunction "C_6") (pintype "passive"))
      (node (ref "U6") (pin "6") (pinfunction "C_6") (pintype "passive"))
      (node (ref "U7") (pin "6") (pinfunction "C_6") (pintype "passive"))
      (node (ref "U8") (pin "6") (pinfunction "C_6") (pintype "passive"))
      (node (ref "U9") (pin "6") (pinfunction "C_6") (pintype "passive"))
    )
    (net (code "116") (name "Net-(U10-IN-)") (class "Default")
      (node (ref "C8") (pin "2") (pinfunction "2_2") (pintype "passive"))
      (node (ref "R46") (pin "1") (pinfunction "1_1") (pintype "passive"))
      (node (ref "R49") (pin "2") (pinfunction "2_2") (pintype "passive"))
      (node (ref "U1") (pin "1") (pinfunction "C_1") (pintype "passive"))
      (node (ref "U10") (pin "2") (pinfunction "IN-_2") (pintype "input"))
      (node (ref "U2") (pin "1") (pinfunction "C_1") (pintype "passive"))
      (node (ref "U3") (pin "1") (pinfunction "C_1") (pintype "passive"))
      (node (ref "U4") (pin "1") (pinfunction "C_1") (pintype "passive"))
      (node (ref "U5") (pin "1") (pinfunction "C_1") (pintype "passive"))
      (node (ref "U6") (pin "1") (pinfunction "C_1") (pintype "passive"))
      (node (ref "U7") (pin "1") (pinfunction "C_1") (pintype "passive"))
      (node (ref "U8") (pin "1") (pinfunction "C_1") (pintype "passive"))
      (node (ref "U9") (pin "1") (pinfunction "C_1") (pintype "passive"))
    )
    (net (code "117") (name "Net-(U10-OUT)") (class "Default")
      (node (ref "C8") (pin "1") (pinfunction "1_1") (pintype "passive"))
      (node (ref "R49") (pin "1") (pinfunction "1_1") (pintype "passive"))
      (node (ref "R51") (pin "2") (pinfunction "2_2") (pintype "passive"))
      (node (ref "U10") (pin "6") (pinfunction "OUT_6") (pintype "output"))
    )
    (net (code "118") (name "Net-(U11-VREF)") (class "Default")
      (node (ref "R25") (pin "2") (pinfunction "2_2") (pintype "passive"))
      (node (ref "R26") (pin "1") (pinfunction "1_1") (pintype "passive"))
      (node (ref "U11") (pin "1") (pinfunction "VREF_1") (pintype "input"))
    )
    (net (code "119") (name "Net-(U13A-IN+)") (class "Default")
      (node (ref "R72") (pin "1") (pinfunction "1_1") (pintype "passive"))
      (node (ref "R73") (pin "2") (pinfunction "2_2") (pintype "passive"))
      (node (ref "U13") (pin "3") (pinfunction "IN+_3") (pintype "input"))
    )
    (net (code "120") (name "Net-(U13A-IN-)") (class "Default")
      (node (ref "R70") (pin "1") (pinfunction "1_1") (pintype "passive"))
      (node (ref "R71") (pin "2") (pinfunction "2_2") (pintype "passive"))
      (node (ref "U13") (pin "2") (pinfunction "IN-_2") (pintype "input"))
    )
    (net (code "121") (name "Net-(U13B-IN-)") (class "Default")
      (node (ref "R74") (pin "1") (pinfunction "1_1") (pintype "passive"))
      (node (ref "R80") (pin "2") (pinfunction "2_2") (pintype "passive"))
      (node (ref "R81") (pin "2") (pinfunction "2_2") (pintype "passive"))
      (node (ref "U13") (pin "6") (pinfunction "IN-_6") (pintype "input"))
      (node (ref "U14") (pin "12") (pinfunction "OUT2_12") (pintype "output"))
    )
    (net (code "122") (name "Net-(U13B-OUT)") (class "Default")
      (node (ref "R71") (pin "1") (pinfunction "1_1") (pintype "passive"))
      (node (ref "R74") (pin "2") (pinfunction "2_2") (pintype "passive"))
      (node (ref "U13") (pin "7") (pinfunction "OUT_7") (pintype "output"))
    )
    (net (code "123") (name "Net-(U14-IN1+)") (class "Default")
      (node (ref "R86") (pin "1") (pinfunction "1_1") (pintype "passive"))
      (node (ref "R87") (pin "2") (pinfunction "2_2") (pintype "passive"))
      (node (ref "U14") (pin "3") (pinfunction "IN1+_3") (pintype "input"))
    )
    (net (code "124") (name "Net-(U14-IN2+)") (class "Default")
      (node (ref "R82") (pin "2") (pinfunction "2_2") (pintype "passive"))
      (node (ref "R83") (pin "1") (pinfunction "1_1") (pintype "passive"))
      (node (ref "U14") (pin "14") (pinfunction "IN2+_14") (pintype "input"))
    )
    (net (code "125") (name "Net-(U14-OUT1)") (class "Default")
      (node (ref "C10") (pin "2") (pinfunction "2_2") (pintype "passive"))
      (node (ref "U14") (pin "5") (pinfunction "OUT1_5") (pintype "output"))
      (node (ref "U15") (pin "6") (pinfunction "IN-_6") (pintype "input"))
    )
    (net (code "126") (name "Net-(U15A-IN+)") (class "Default")
      (node (ref "R88") (pin "1") (pinfunction "1_1") (pintype "passive"))
      (node (ref "R89") (pin "1") (pinfunction "1_1") (pintype "passive"))
      (node (ref "R90") (pin "1") (pinfunction "1_1") (pintype "passive"))
      (node (ref "U15") (pin "3") (pinfunction "IN+_3") (pintype "input"))
    )
    (net (code "127") (name "Net-(U15A-OUT)") (class "Default")
      (node (ref "R87") (pin "1") (pinfunction "1_1") (pintype "passive"))
      (node (ref "R88") (pin "2") (pinfunction "2_2") (pintype "passive"))
      (node (ref "U15") (pin "1") (pinfunction "OUT_1") (pintype "output"))
    )
    (net (code "128") (name "Net-(U15B-OUT)") (class "Default")
      (node (ref "C10") (pin "1") (pinfunction "1_1") (pintype "passive"))
      (node (ref "R83") (pin "2") (pinfunction "2_2") (pintype "passive"))
      (node (ref "R89") (pin "2") (pinfunction "2_2") (pintype "passive"))
      (node (ref "U15") (pin "7") (pinfunction "OUT_7") (pintype "output"))
    )
    (net (code "129") (name "unconnected-(AC-Pad3)") (class "Default")
      (node (ref "AC") (pin "3") (pinfunction "3_3") (pintype "passive"))
    )
    (net (code "130") (name "unconnected-(U10-NC-Pad8)") (class "Default")
      (node (ref "U10") (pin "8") (pinfunction "NC_8") (pintype "passive"))
    )
    (net (code "131") (name "unconnected-(U10-OS_TRIM-Pad1)") (class "Default")
      (node (ref "U10") (pin "1") (pinfunction "OS_TRIM_1") (pintype "passive"))
    )
    (net (code "132") (name "unconnected-(U10-OS_TRIM-Pad5)") (class "Default")
      (node (ref "U10") (pin "5") (pinfunction "OS_TRIM_5") (pintype "passive"))
    )
    (net (code "133") (name "unconnected-(U14-BUF_OUT1-Pad8)") (class "Default")
      (node (ref "U14") (pin "8") (pinfunction "BUF_OUT1_8") (pintype "passive"))
    )
    (net (code "134") (name "unconnected-(U14-BUF_OUT2-Pad9)") (class "Default")
      (node (ref "U14") (pin "9") (pinfunction "BUF_OUT2_9") (pintype "passive"))
    )
    (net (code "135") (name "unconnected-(U14-DIODE_BIAS1-Pad2)") (class "Default")
      (node (ref "U14") (pin "2") (pinfunction "DIODE_BIAS1_2") (pintype "passive"))
    )
    (net (code "136") (name "unconnected-(U14-DIODE_BIAS2-Pad15)") (class "Default")
      (node (ref "U14") (pin "15") (pinfunction "DIODE_BIAS2_15") (pintype "passive"))
    )
  )
)
